# DNVT_box4t.net
KiCad netlist of a schematic drawn in EAGLE
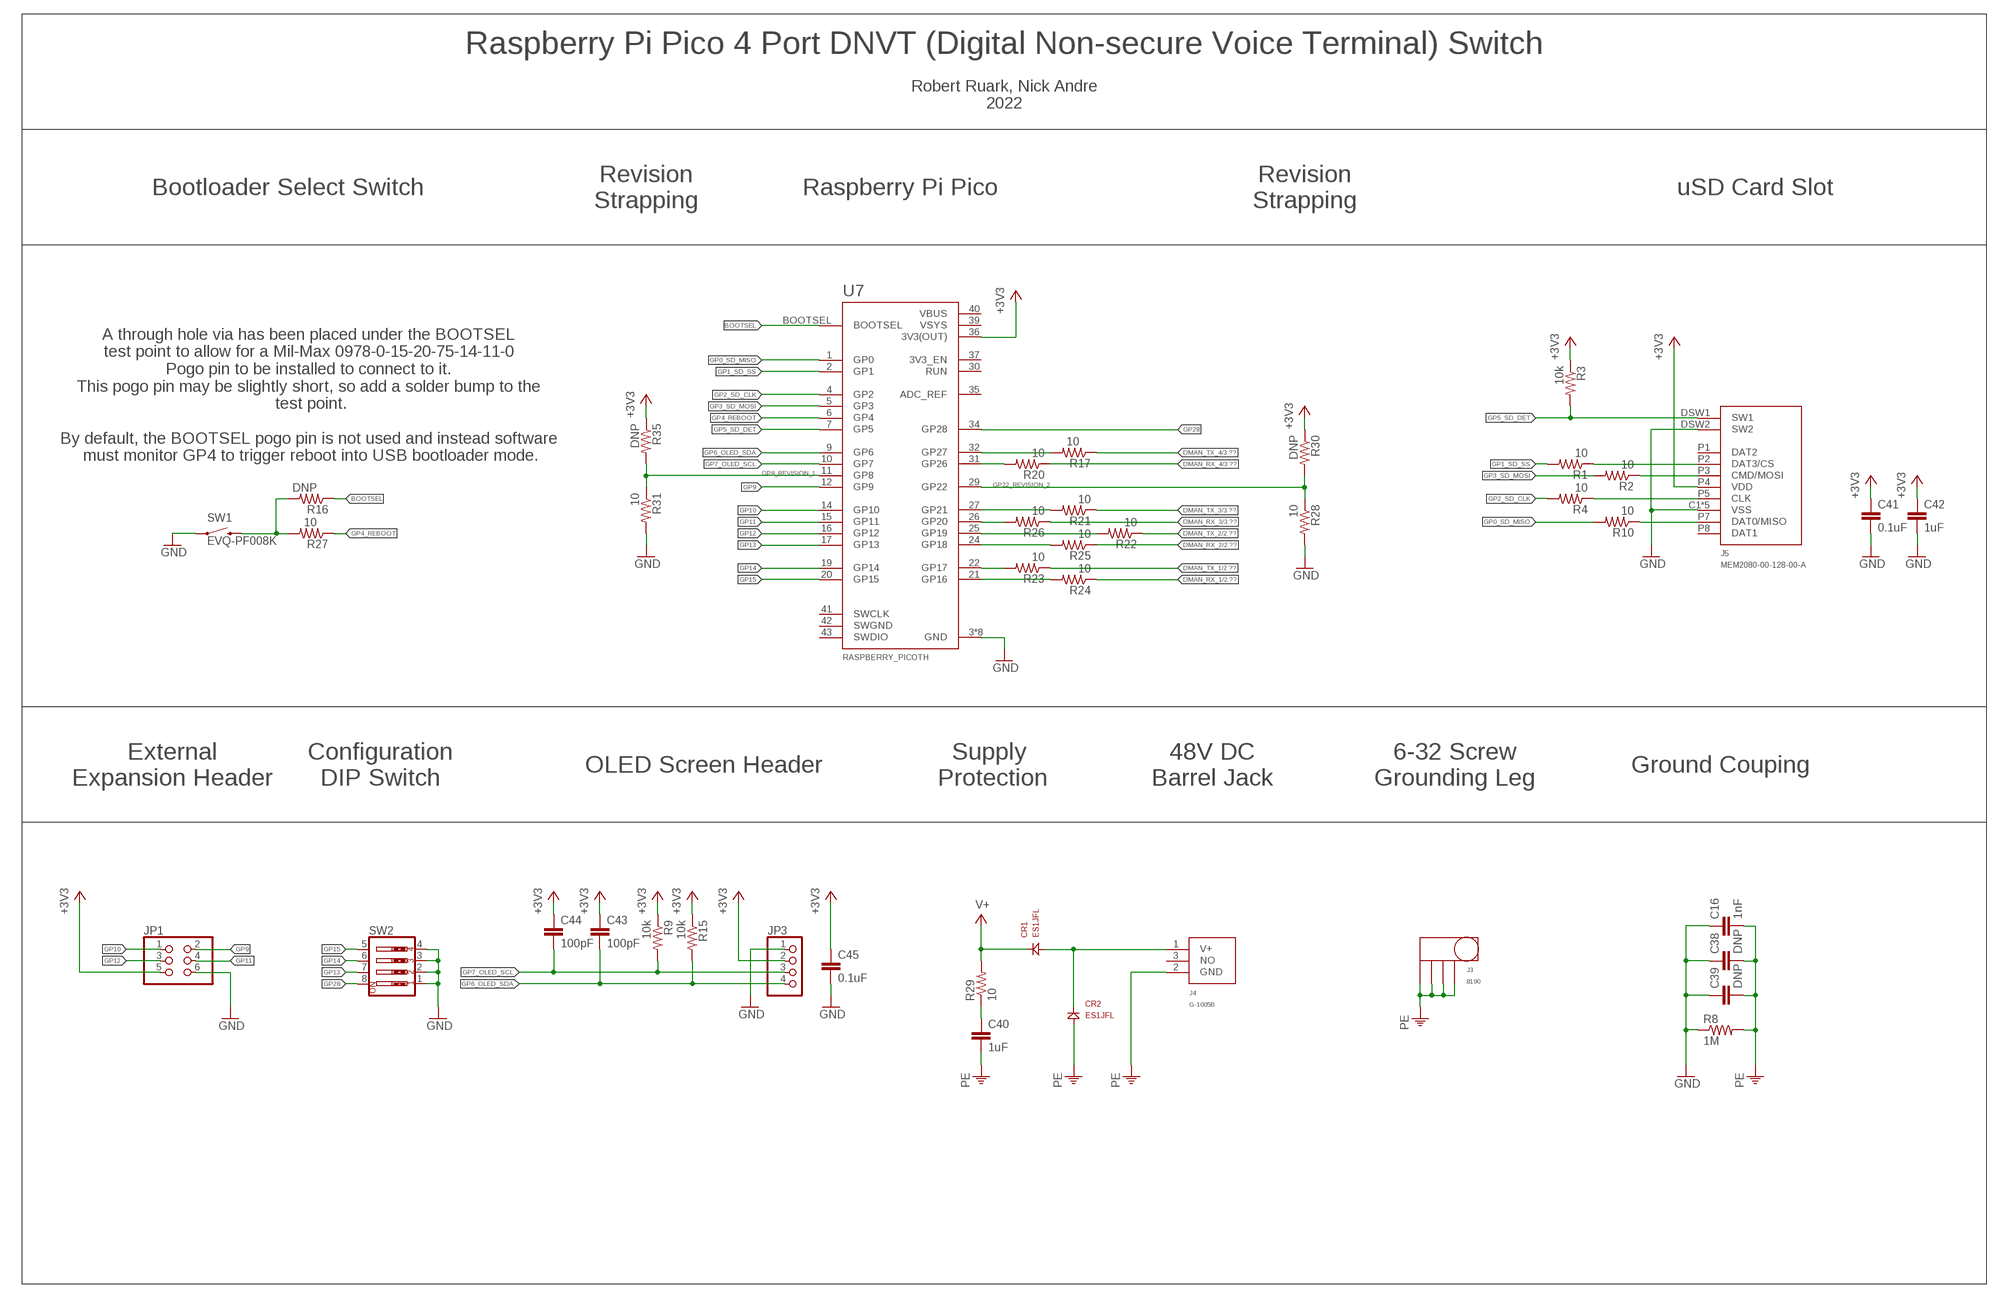
[diagram p0: schematic, sheet 1]
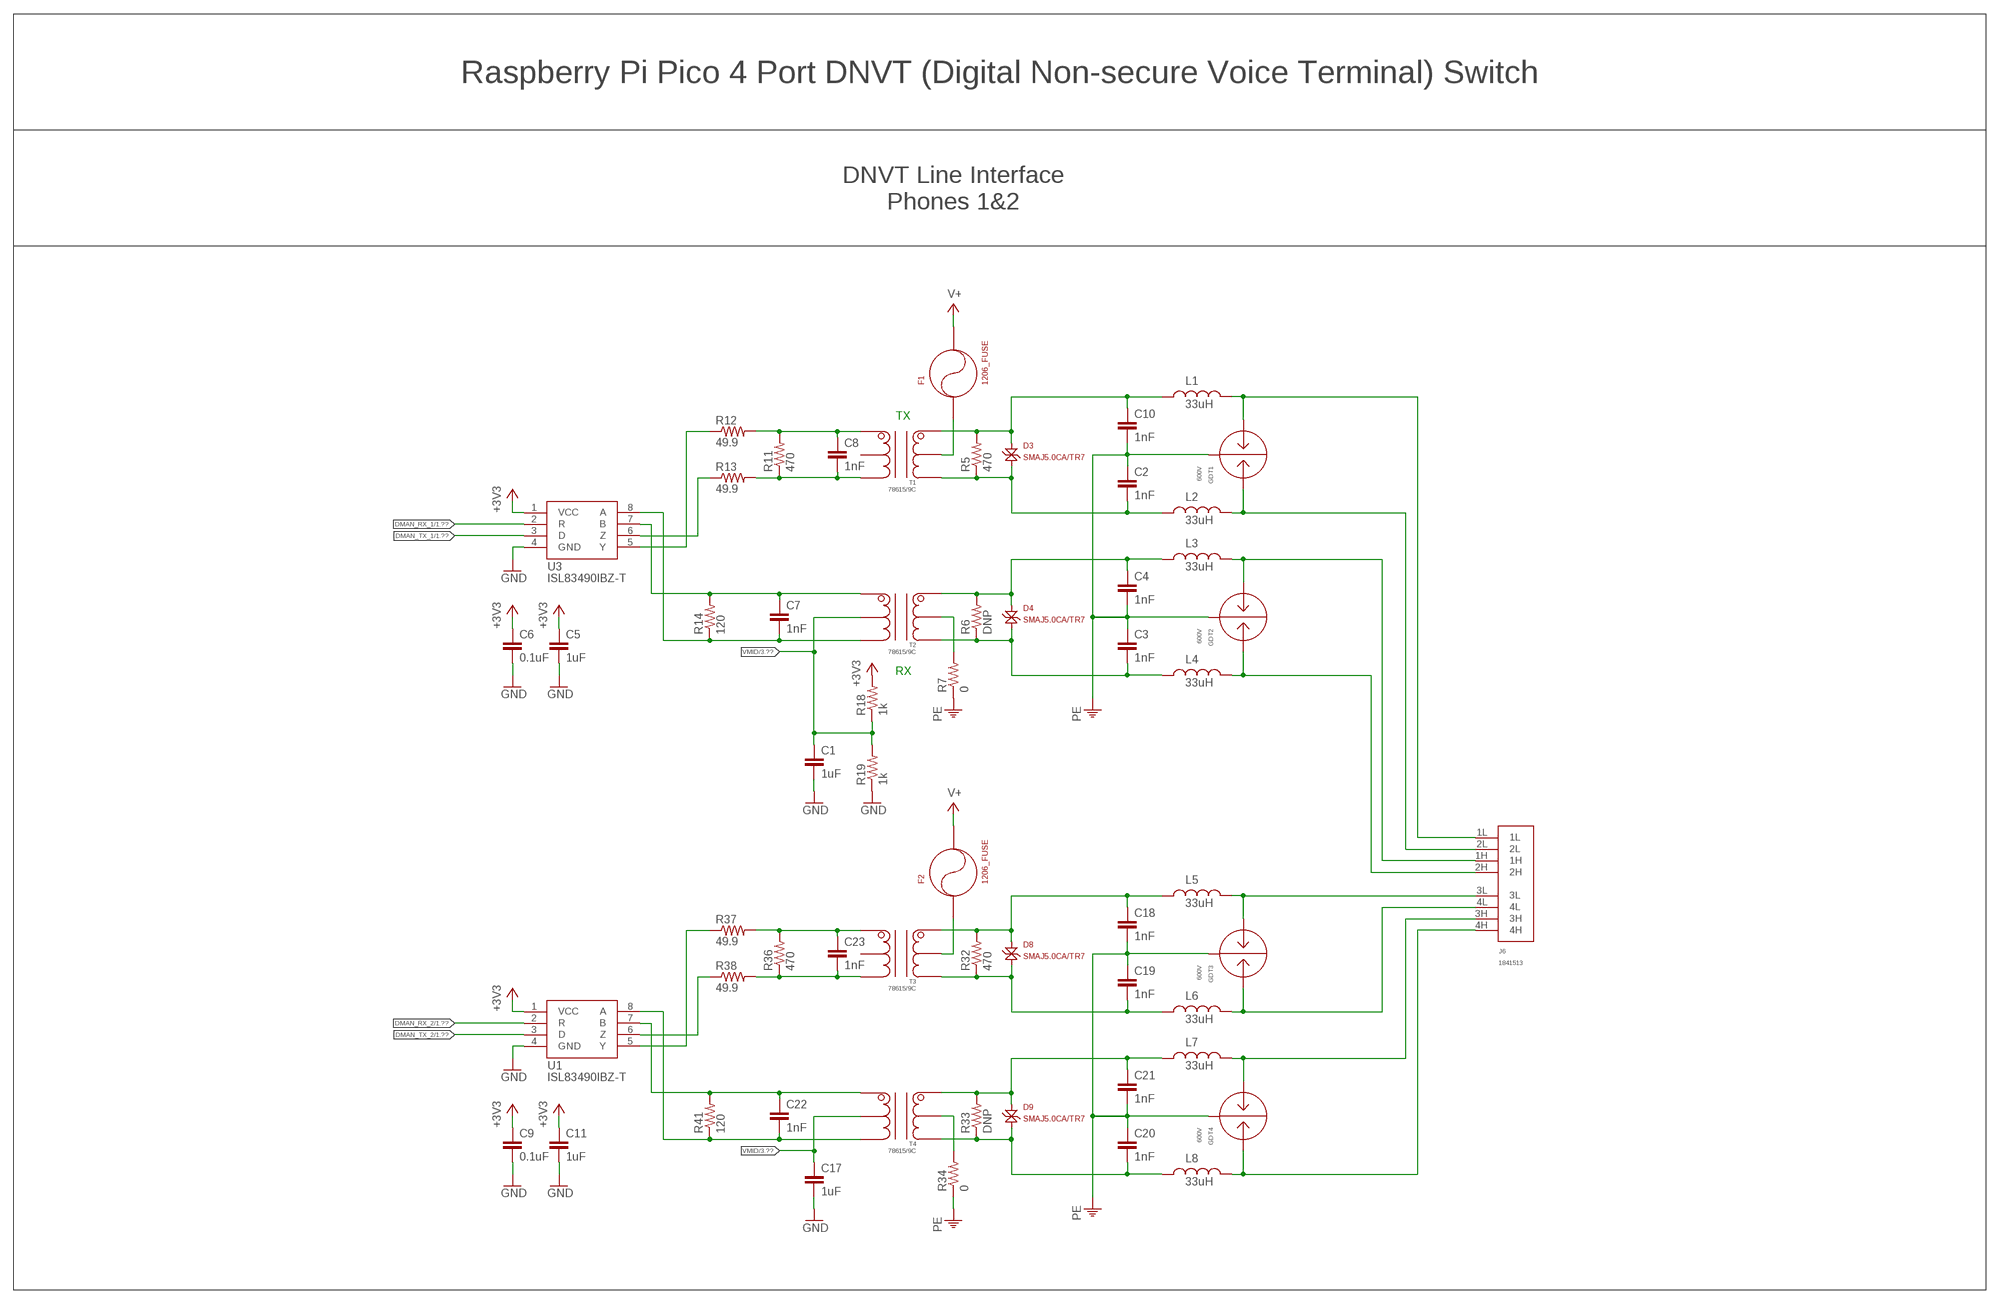
[diagram p1: schematic, sheet 2]
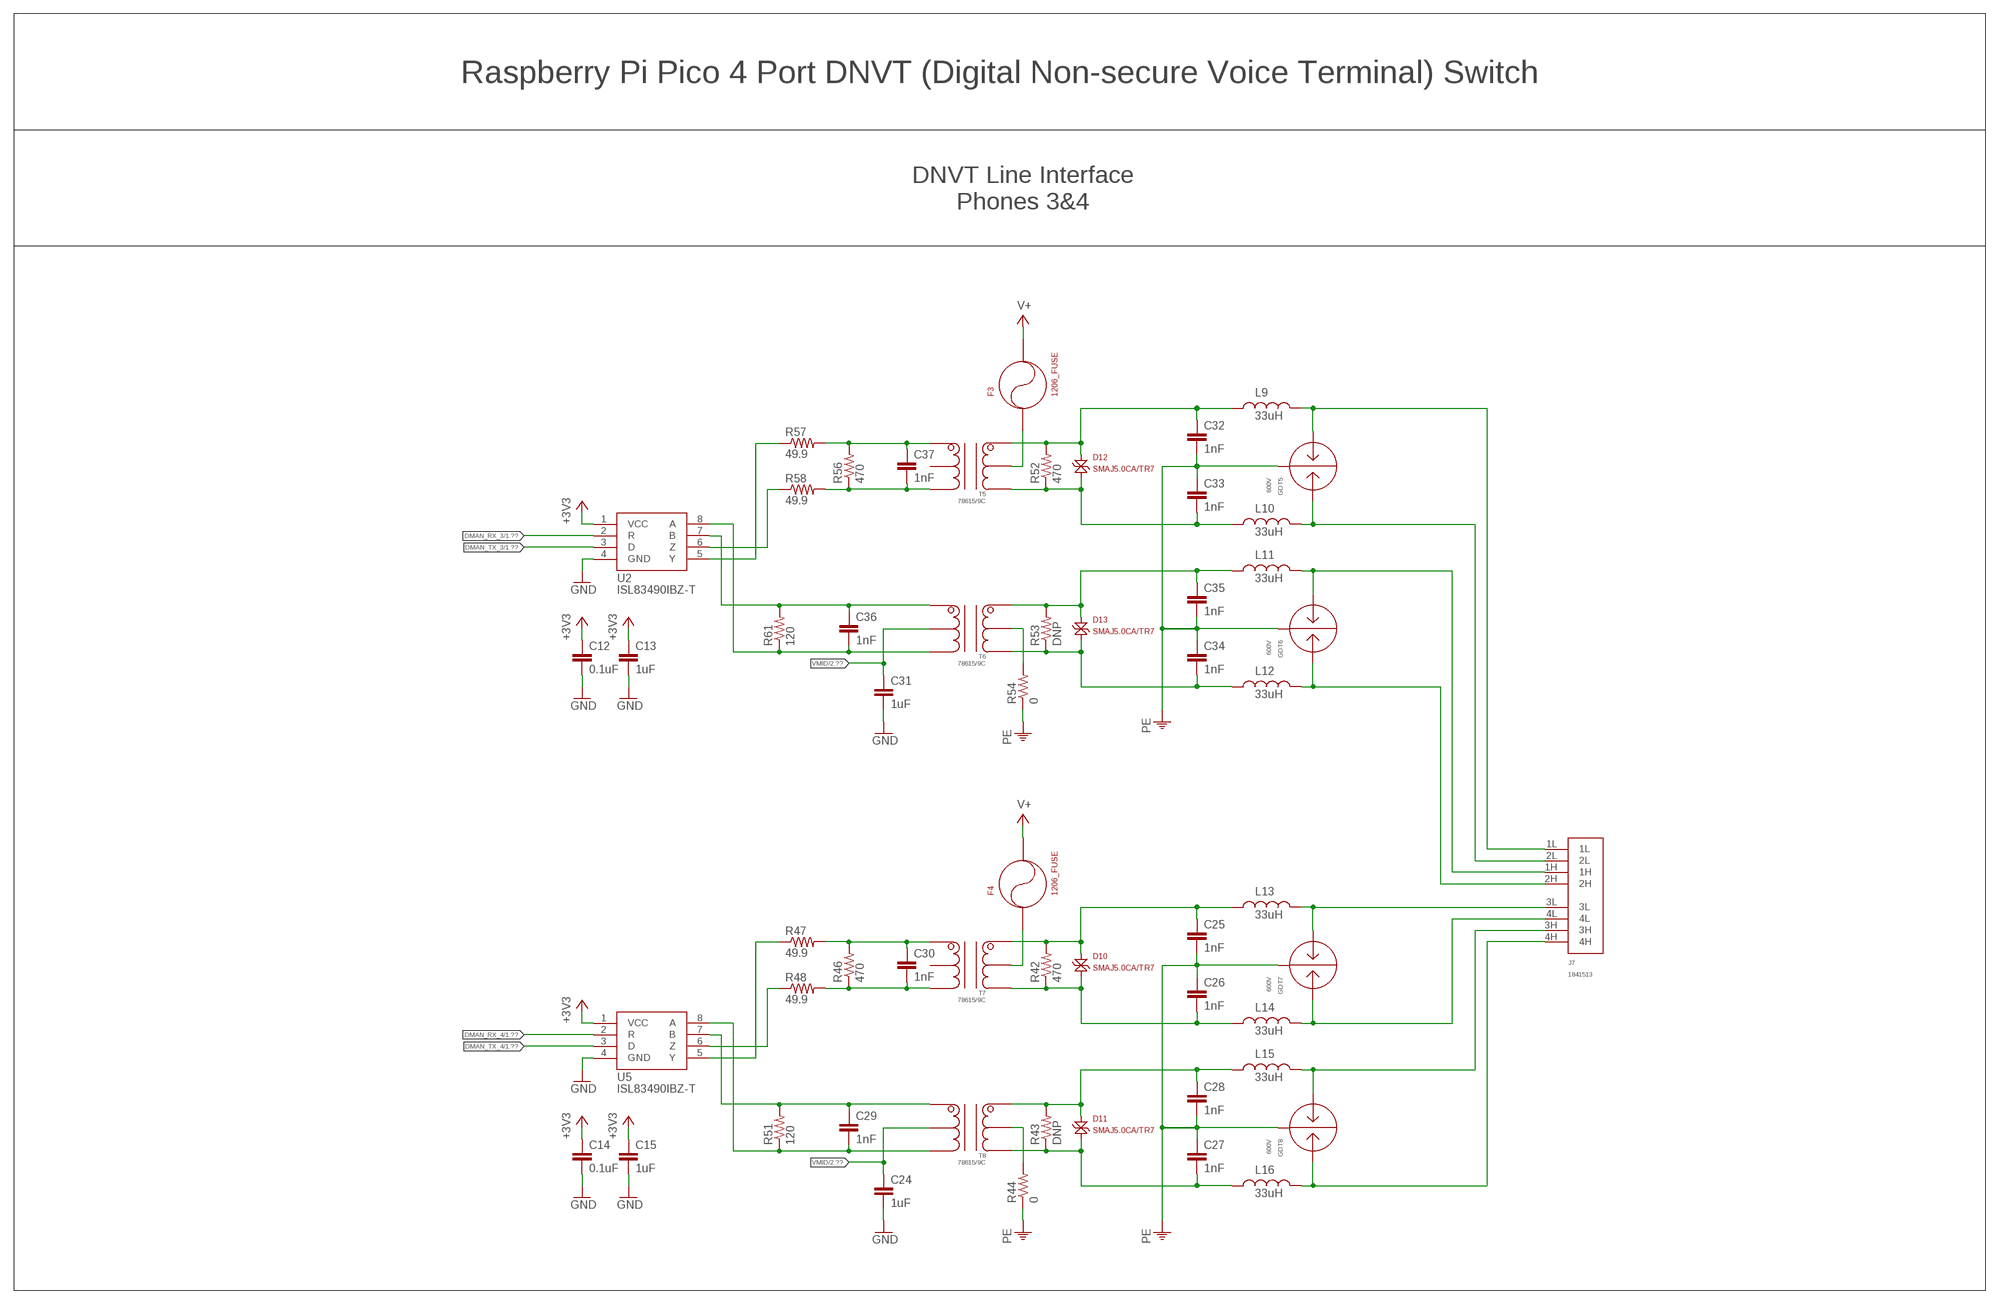
[diagram p2: schematic, sheet 3]

(export (version "E")
  (design (tool "Eeschema 10.0.6"))
  (components
    (comp (ref "C1")
      (value "1uF")
      (footprint "eagle-import:0805")
      (libsource (lib "eagle-import") (part "0805_CAPACITOR"))
    )
    (comp (ref "C2")
      (value "1nF")
      (footprint "eagle-import:0805")
      (libsource (lib "eagle-import") (part "0805_CAPACITOR"))
    )
    (comp (ref "C3")
      (value "1nF")
      (footprint "eagle-import:0805")
      (libsource (lib "eagle-import") (part "0805_CAPACITOR"))
    )
    (comp (ref "C4")
      (value "1nF")
      (footprint "eagle-import:0805")
      (libsource (lib "eagle-import") (part "0805_CAPACITOR"))
    )
    (comp (ref "C5")
      (value "1uF")
      (footprint "eagle-import:0805")
      (libsource (lib "eagle-import") (part "0805_CAPACITOR"))
    )
    (comp (ref "C6")
      (value "0.1uF")
      (footprint "eagle-import:0603")
      (libsource (lib "eagle-import") (part "0603_CAPACITOR"))
    )
    (comp (ref "C7")
      (value "1nF")
      (footprint "eagle-import:0805")
      (libsource (lib "eagle-import") (part "0805_CAPACITOR"))
    )
    (comp (ref "C8")
      (value "1nF")
      (footprint "eagle-import:0805")
      (libsource (lib "eagle-import") (part "0805_CAPACITOR"))
    )
    (comp (ref "C9")
      (value "0.1uF")
      (footprint "eagle-import:0603")
      (libsource (lib "eagle-import") (part "0603_CAPACITOR"))
    )
    (comp (ref "C10")
      (value "1nF")
      (footprint "eagle-import:0805")
      (libsource (lib "eagle-import") (part "0805_CAPACITOR"))
    )
    (comp (ref "C11")
      (value "1uF")
      (footprint "eagle-import:0805")
      (libsource (lib "eagle-import") (part "0805_CAPACITOR"))
    )
    (comp (ref "C17")
      (value "1uF")
      (footprint "eagle-import:0805")
      (libsource (lib "eagle-import") (part "0805_CAPACITOR"))
    )
    (comp (ref "C18")
      (value "1nF")
      (footprint "eagle-import:0805")
      (libsource (lib "eagle-import") (part "0805_CAPACITOR"))
    )
    (comp (ref "C19")
      (value "1nF")
      (footprint "eagle-import:0805")
      (libsource (lib "eagle-import") (part "0805_CAPACITOR"))
    )
    (comp (ref "C20")
      (value "1nF")
      (footprint "eagle-import:0805")
      (libsource (lib "eagle-import") (part "0805_CAPACITOR"))
    )
    (comp (ref "C21")
      (value "1nF")
      (footprint "eagle-import:0805")
      (libsource (lib "eagle-import") (part "0805_CAPACITOR"))
    )
    (comp (ref "C22")
      (value "1nF")
      (footprint "eagle-import:0805")
      (libsource (lib "eagle-import") (part "0805_CAPACITOR"))
    )
    (comp (ref "C23")
      (value "1nF")
      (footprint "eagle-import:0805")
      (libsource (lib "eagle-import") (part "0805_CAPACITOR"))
    )
    (comp (ref "D3")
      (value "SMAJ5.0CA/TR7")
      (footprint "eagle-import:DO-214AC_NO_POL")
      (libsource (lib "eagle-import") (part "SMAJ5.0CA/TR7"))
    )
    (comp (ref "D4")
      (value "SMAJ5.0CA/TR7")
      (footprint "eagle-import:DO-214AC_NO_POL")
      (libsource (lib "eagle-import") (part "SMAJ5.0CA/TR7"))
    )
    (comp (ref "D8")
      (value "SMAJ5.0CA/TR7")
      (footprint "eagle-import:DO-214AC_NO_POL")
      (libsource (lib "eagle-import") (part "SMAJ5.0CA/TR7"))
    )
    (comp (ref "D9")
      (value "SMAJ5.0CA/TR7")
      (footprint "eagle-import:DO-214AC_NO_POL")
      (libsource (lib "eagle-import") (part "SMAJ5.0CA/TR7"))
    )
    (comp (ref "F1")
      (value "1206_FUSE")
      (footprint "eagle-import:1206")
      (libsource (lib "eagle-import") (part "1206_FUSE"))
    )
    (comp (ref "F2")
      (value "1206_FUSE")
      (footprint "eagle-import:1206")
      (libsource (lib "eagle-import") (part "1206_FUSE"))
    )
    (comp (ref "GDT1")
      (value "600V")
      (footprint "eagle-import:2036_GDT")
      (fields (field (name "PARTNO") "2036-60-SM-RPLFCT-ND"))
      (libsource (lib "eagle-import") (part "2036-60-SM-RPLF"))
    )
    (comp (ref "GDT2")
      (value "600V")
      (footprint "eagle-import:2036_GDT")
      (fields (field (name "PARTNO") "2036-60-SM-RPLFCT-ND"))
      (libsource (lib "eagle-import") (part "2036-60-SM-RPLF"))
    )
    (comp (ref "GDT3")
      (value "600V")
      (footprint "eagle-import:2036_GDT")
      (fields (field (name "PARTNO") "2036-60-SM-RPLFCT-ND"))
      (libsource (lib "eagle-import") (part "2036-60-SM-RPLF"))
    )
    (comp (ref "GDT4")
      (value "600V")
      (footprint "eagle-import:2036_GDT")
      (fields (field (name "PARTNO") "2036-60-SM-RPLFCT-ND"))
      (libsource (lib "eagle-import") (part "2036-60-SM-RPLF"))
    )
    (comp (ref "J6")
      (value "1841513")
      (footprint "eagle-import:1841513")
      (fields (field (name "PARTNO") "277-10317-ND"))
      (libsource (lib "eagle-import") (part "1841513"))
    )
    (comp (ref "L1")
      (value "33uH")
      (footprint "eagle-import:SDR0403")
      (fields (field (name "PARTNO") "SDR0403-330KLCT-ND"))
      (libsource (lib "eagle-import") (part "SDR0403-330KL"))
    )
    (comp (ref "L2")
      (value "33uH")
      (footprint "eagle-import:SDR0403")
      (fields (field (name "PARTNO") "SDR0403-330KLCT-ND"))
      (libsource (lib "eagle-import") (part "SDR0403-330KL"))
    )
    (comp (ref "L3")
      (value "33uH")
      (footprint "eagle-import:SDR0403")
      (fields (field (name "PARTNO") "SDR0403-330KLCT-ND"))
      (libsource (lib "eagle-import") (part "SDR0403-330KL"))
    )
    (comp (ref "L4")
      (value "33uH")
      (footprint "eagle-import:SDR0403")
      (fields (field (name "PARTNO") "SDR0403-330KLCT-ND"))
      (libsource (lib "eagle-import") (part "SDR0403-330KL"))
    )
    (comp (ref "L5")
      (value "33uH")
      (footprint "eagle-import:SDR0403")
      (fields (field (name "PARTNO") "SDR0403-330KLCT-ND"))
      (libsource (lib "eagle-import") (part "SDR0403-330KL"))
    )
    (comp (ref "L6")
      (value "33uH")
      (footprint "eagle-import:SDR0403")
      (fields (field (name "PARTNO") "SDR0403-330KLCT-ND"))
      (libsource (lib "eagle-import") (part "SDR0403-330KL"))
    )
    (comp (ref "L7")
      (value "33uH")
      (footprint "eagle-import:SDR0403")
      (fields (field (name "PARTNO") "SDR0403-330KLCT-ND"))
      (libsource (lib "eagle-import") (part "SDR0403-330KL"))
    )
    (comp (ref "L8")
      (value "33uH")
      (footprint "eagle-import:SDR0403")
      (fields (field (name "PARTNO") "SDR0403-330KLCT-ND"))
      (libsource (lib "eagle-import") (part "SDR0403-330KL"))
    )
    (comp (ref "R5")
      (value "470")
      (footprint "eagle-import:R0805")
      (libsource (lib "eagle-import") (part "R-US_R0805"))
    )
    (comp (ref "R6")
      (value "DNP")
      (footprint "eagle-import:R0805")
      (libsource (lib "eagle-import") (part "R-US_R0805"))
    )
    (comp (ref "R7")
      (value "0")
      (footprint "eagle-import:R0805")
      (libsource (lib "eagle-import") (part "R-US_R0805"))
    )
    (comp (ref "R11")
      (value "470")
      (footprint "eagle-import:R0805")
      (libsource (lib "eagle-import") (part "R-US_R0805"))
    )
    (comp (ref "R12")
      (value "49.9")
      (footprint "eagle-import:R0805")
      (libsource (lib "eagle-import") (part "R-US_R0805"))
    )
    (comp (ref "R13")
      (value "49.9")
      (footprint "eagle-import:R0805")
      (libsource (lib "eagle-import") (part "R-US_R0805"))
    )
    (comp (ref "R14")
      (value "120")
      (footprint "eagle-import:1206")
      (libsource (lib "eagle-import") (part "1206_RESISTOR"))
    )
    (comp (ref "R18")
      (value "1k")
      (footprint "eagle-import:0603")
      (libsource (lib "eagle-import") (part "0603_RESISTOR"))
    )
    (comp (ref "R19")
      (value "1k")
      (footprint "eagle-import:0603")
      (libsource (lib "eagle-import") (part "0603_RESISTOR"))
    )
    (comp (ref "R32")
      (value "470")
      (footprint "eagle-import:R0805")
      (libsource (lib "eagle-import") (part "R-US_R0805"))
    )
    (comp (ref "R33")
      (value "DNP")
      (footprint "eagle-import:R0805")
      (libsource (lib "eagle-import") (part "R-US_R0805"))
    )
    (comp (ref "R34")
      (value "0")
      (footprint "eagle-import:R0805")
      (libsource (lib "eagle-import") (part "R-US_R0805"))
    )
    (comp (ref "R36")
      (value "470")
      (footprint "eagle-import:R0805")
      (libsource (lib "eagle-import") (part "R-US_R0805"))
    )
    (comp (ref "R37")
      (value "49.9")
      (footprint "eagle-import:R0805")
      (libsource (lib "eagle-import") (part "R-US_R0805"))
    )
    (comp (ref "R38")
      (value "49.9")
      (footprint "eagle-import:R0805")
      (libsource (lib "eagle-import") (part "R-US_R0805"))
    )
    (comp (ref "R41")
      (value "120")
      (footprint "eagle-import:1206")
      (libsource (lib "eagle-import") (part "1206_RESISTOR"))
    )
    (comp (ref "T1")
      (value "78615/9C")
      (footprint "eagle-import:786T")
      (libsource (lib "eagle-import") (part "78615/9C"))
    )
    (comp (ref "T2")
      (value "78615/9C")
      (footprint "eagle-import:786T")
      (libsource (lib "eagle-import") (part "78615/9C"))
    )
    (comp (ref "T3")
      (value "78615/9C")
      (footprint "eagle-import:786T")
      (libsource (lib "eagle-import") (part "78615/9C"))
    )
    (comp (ref "T4")
      (value "78615/9C")
      (footprint "eagle-import:786T")
      (libsource (lib "eagle-import") (part "78615/9C"))
    )
    (comp (ref "U1")
      (value "ISL83490IBZ-T")
      (footprint "eagle-import:SOIC8")
      (fields (field (name "PARTNO") "ISL83490IBZ-TCT-ND"))
      (libsource (lib "eagle-import") (part "ISL83490IBZ-T"))
    )
    (comp (ref "U3")
      (value "ISL83490IBZ-T")
      (footprint "eagle-import:SOIC8")
      (fields (field (name "PARTNO") "ISL83490IBZ-TCT-ND"))
      (libsource (lib "eagle-import") (part "ISL83490IBZ-T"))
    )
    (comp (ref "C12")
      (value "0.1uF")
      (footprint "eagle-import:0603")
      (libsource (lib "eagle-import") (part "0603_CAPACITOR"))
    )
    (comp (ref "C13")
      (value "1uF")
      (footprint "eagle-import:0805")
      (libsource (lib "eagle-import") (part "0805_CAPACITOR"))
    )
    (comp (ref "C14")
      (value "0.1uF")
      (footprint "eagle-import:0603")
      (libsource (lib "eagle-import") (part "0603_CAPACITOR"))
    )
    (comp (ref "C15")
      (value "1uF")
      (footprint "eagle-import:0805")
      (libsource (lib "eagle-import") (part "0805_CAPACITOR"))
    )
    (comp (ref "C24")
      (value "1uF")
      (footprint "eagle-import:0805")
      (libsource (lib "eagle-import") (part "0805_CAPACITOR"))
    )
    (comp (ref "C25")
      (value "1nF")
      (footprint "eagle-import:0805")
      (libsource (lib "eagle-import") (part "0805_CAPACITOR"))
    )
    (comp (ref "C26")
      (value "1nF")
      (footprint "eagle-import:0805")
      (libsource (lib "eagle-import") (part "0805_CAPACITOR"))
    )
    (comp (ref "C27")
      (value "1nF")
      (footprint "eagle-import:0805")
      (libsource (lib "eagle-import") (part "0805_CAPACITOR"))
    )
    (comp (ref "C28")
      (value "1nF")
      (footprint "eagle-import:0805")
      (libsource (lib "eagle-import") (part "0805_CAPACITOR"))
    )
    (comp (ref "C29")
      (value "1nF")
      (footprint "eagle-import:0805")
      (libsource (lib "eagle-import") (part "0805_CAPACITOR"))
    )
    (comp (ref "C30")
      (value "1nF")
      (footprint "eagle-import:0805")
      (libsource (lib "eagle-import") (part "0805_CAPACITOR"))
    )
    (comp (ref "C31")
      (value "1uF")
      (footprint "eagle-import:0805")
      (libsource (lib "eagle-import") (part "0805_CAPACITOR"))
    )
    (comp (ref "C32")
      (value "1nF")
      (footprint "eagle-import:0805")
      (libsource (lib "eagle-import") (part "0805_CAPACITOR"))
    )
    (comp (ref "C33")
      (value "1nF")
      (footprint "eagle-import:0805")
      (libsource (lib "eagle-import") (part "0805_CAPACITOR"))
    )
    (comp (ref "C34")
      (value "1nF")
      (footprint "eagle-import:0805")
      (libsource (lib "eagle-import") (part "0805_CAPACITOR"))
    )
    (comp (ref "C35")
      (value "1nF")
      (footprint "eagle-import:0805")
      (libsource (lib "eagle-import") (part "0805_CAPACITOR"))
    )
    (comp (ref "C36")
      (value "1nF")
      (footprint "eagle-import:0805")
      (libsource (lib "eagle-import") (part "0805_CAPACITOR"))
    )
    (comp (ref "C37")
      (value "1nF")
      (footprint "eagle-import:0805")
      (libsource (lib "eagle-import") (part "0805_CAPACITOR"))
    )
    (comp (ref "D10")
      (value "SMAJ5.0CA/TR7")
      (footprint "eagle-import:DO-214AC_NO_POL")
      (libsource (lib "eagle-import") (part "SMAJ5.0CA/TR7"))
    )
    (comp (ref "D11")
      (value "SMAJ5.0CA/TR7")
      (footprint "eagle-import:DO-214AC_NO_POL")
      (libsource (lib "eagle-import") (part "SMAJ5.0CA/TR7"))
    )
    (comp (ref "D12")
      (value "SMAJ5.0CA/TR7")
      (footprint "eagle-import:DO-214AC_NO_POL")
      (libsource (lib "eagle-import") (part "SMAJ5.0CA/TR7"))
    )
    (comp (ref "D13")
      (value "SMAJ5.0CA/TR7")
      (footprint "eagle-import:DO-214AC_NO_POL")
      (libsource (lib "eagle-import") (part "SMAJ5.0CA/TR7"))
    )
    (comp (ref "F3")
      (value "1206_FUSE")
      (footprint "eagle-import:1206")
      (libsource (lib "eagle-import") (part "1206_FUSE"))
    )
    (comp (ref "F4")
      (value "1206_FUSE")
      (footprint "eagle-import:1206")
      (libsource (lib "eagle-import") (part "1206_FUSE"))
    )
    (comp (ref "GDT5")
      (value "600V")
      (footprint "eagle-import:2036_GDT")
      (fields (field (name "PARTNO") "2036-60-SM-RPLFCT-ND"))
      (libsource (lib "eagle-import") (part "2036-60-SM-RPLF"))
    )
    (comp (ref "GDT6")
      (value "600V")
      (footprint "eagle-import:2036_GDT")
      (fields (field (name "PARTNO") "2036-60-SM-RPLFCT-ND"))
      (libsource (lib "eagle-import") (part "2036-60-SM-RPLF"))
    )
    (comp (ref "GDT7")
      (value "600V")
      (footprint "eagle-import:2036_GDT")
      (fields (field (name "PARTNO") "2036-60-SM-RPLFCT-ND"))
      (libsource (lib "eagle-import") (part "2036-60-SM-RPLF"))
    )
    (comp (ref "GDT8")
      (value "600V")
      (footprint "eagle-import:2036_GDT")
      (fields (field (name "PARTNO") "2036-60-SM-RPLFCT-ND"))
      (libsource (lib "eagle-import") (part "2036-60-SM-RPLF"))
    )
    (comp (ref "J7")
      (value "1841513")
      (footprint "eagle-import:1841513")
      (fields (field (name "PARTNO") "277-10317-ND"))
      (libsource (lib "eagle-import") (part "1841513"))
    )
    (comp (ref "L9")
      (value "33uH")
      (footprint "eagle-import:SDR0403")
      (fields (field (name "PARTNO") "SDR0403-330KLCT-ND"))
      (libsource (lib "eagle-import") (part "SDR0403-330KL"))
    )
    (comp (ref "L10")
      (value "33uH")
      (footprint "eagle-import:SDR0403")
      (fields (field (name "PARTNO") "SDR0403-330KLCT-ND"))
      (libsource (lib "eagle-import") (part "SDR0403-330KL"))
    )
    (comp (ref "L11")
      (value "33uH")
      (footprint "eagle-import:SDR0403")
      (fields (field (name "PARTNO") "SDR0403-330KLCT-ND"))
      (libsource (lib "eagle-import") (part "SDR0403-330KL"))
    )
    (comp (ref "L12")
      (value "33uH")
      (footprint "eagle-import:SDR0403")
      (fields (field (name "PARTNO") "SDR0403-330KLCT-ND"))
      (libsource (lib "eagle-import") (part "SDR0403-330KL"))
    )
    (comp (ref "L13")
      (value "33uH")
      (footprint "eagle-import:SDR0403")
      (fields (field (name "PARTNO") "SDR0403-330KLCT-ND"))
      (libsource (lib "eagle-import") (part "SDR0403-330KL"))
    )
    (comp (ref "L14")
      (value "33uH")
      (footprint "eagle-import:SDR0403")
      (fields (field (name "PARTNO") "SDR0403-330KLCT-ND"))
      (libsource (lib "eagle-import") (part "SDR0403-330KL"))
    )
    (comp (ref "L15")
      (value "33uH")
      (footprint "eagle-import:SDR0403")
      (fields (field (name "PARTNO") "SDR0403-330KLCT-ND"))
      (libsource (lib "eagle-import") (part "SDR0403-330KL"))
    )
    (comp (ref "L16")
      (value "33uH")
      (footprint "eagle-import:SDR0403")
      (fields (field (name "PARTNO") "SDR0403-330KLCT-ND"))
      (libsource (lib "eagle-import") (part "SDR0403-330KL"))
    )
    (comp (ref "R42")
      (value "470")
      (footprint "eagle-import:R0805")
      (libsource (lib "eagle-import") (part "R-US_R0805"))
    )
    (comp (ref "R43")
      (value "DNP")
      (footprint "eagle-import:R0805")
      (libsource (lib "eagle-import") (part "R-US_R0805"))
    )
    (comp (ref "R44")
      (value "0")
      (footprint "eagle-import:R0805")
      (libsource (lib "eagle-import") (part "R-US_R0805"))
    )
    (comp (ref "R46")
      (value "470")
      (footprint "eagle-import:R0805")
      (libsource (lib "eagle-import") (part "R-US_R0805"))
    )
    (comp (ref "R47")
      (value "49.9")
      (footprint "eagle-import:R0805")
      (libsource (lib "eagle-import") (part "R-US_R0805"))
    )
    (comp (ref "R48")
      (value "49.9")
      (footprint "eagle-import:R0805")
      (libsource (lib "eagle-import") (part "R-US_R0805"))
    )
    (comp (ref "R51")
      (value "120")
      (footprint "eagle-import:1206")
      (libsource (lib "eagle-import") (part "1206_RESISTOR"))
    )
    (comp (ref "R52")
      (value "470")
      (footprint "eagle-import:R0805")
      (libsource (lib "eagle-import") (part "R-US_R0805"))
    )
    (comp (ref "R53")
      (value "DNP")
      (footprint "eagle-import:R0805")
      (libsource (lib "eagle-import") (part "R-US_R0805"))
    )
    (comp (ref "R54")
      (value "0")
      (footprint "eagle-import:R0805")
      (libsource (lib "eagle-import") (part "R-US_R0805"))
    )
    (comp (ref "R56")
      (value "470")
      (footprint "eagle-import:R0805")
      (libsource (lib "eagle-import") (part "R-US_R0805"))
    )
    (comp (ref "R57")
      (value "49.9")
      (footprint "eagle-import:R0805")
      (libsource (lib "eagle-import") (part "R-US_R0805"))
    )
    (comp (ref "R58")
      (value "49.9")
      (footprint "eagle-import:R0805")
      (libsource (lib "eagle-import") (part "R-US_R0805"))
    )
    (comp (ref "R61")
      (value "120")
      (footprint "eagle-import:1206")
      (libsource (lib "eagle-import") (part "1206_RESISTOR"))
    )
    (comp (ref "T5")
      (value "78615/9C")
      (footprint "eagle-import:786T")
      (libsource (lib "eagle-import") (part "78615/9C"))
    )
    (comp (ref "T6")
      (value "78615/9C")
      (footprint "eagle-import:786T")
      (libsource (lib "eagle-import") (part "78615/9C"))
    )
    (comp (ref "T7")
      (value "78615/9C")
      (footprint "eagle-import:786T")
      (libsource (lib "eagle-import") (part "78615/9C"))
    )
    (comp (ref "T8")
      (value "78615/9C")
      (footprint "eagle-import:786T")
      (libsource (lib "eagle-import") (part "78615/9C"))
    )
    (comp (ref "U2")
      (value "ISL83490IBZ-T")
      (footprint "eagle-import:SOIC8")
      (fields (field (name "PARTNO") "ISL83490IBZ-TCT-ND"))
      (libsource (lib "eagle-import") (part "ISL83490IBZ-T"))
    )
    (comp (ref "U5")
      (value "ISL83490IBZ-T")
      (footprint "eagle-import:SOIC8")
      (fields (field (name "PARTNO") "ISL83490IBZ-TCT-ND"))
      (libsource (lib "eagle-import") (part "ISL83490IBZ-T"))
    )
    (comp (ref "C16")
      (value "1nF")
      (footprint "eagle-import:1206")
      (libsource (lib "eagle-import") (part "1206_CAPACITOR"))
    )
    (comp (ref "C38")
      (value "DNP")
      (footprint "eagle-import:1206")
      (libsource (lib "eagle-import") (part "1206_CAPACITOR"))
    )
    (comp (ref "C39")
      (value "DNP")
      (footprint "eagle-import:1206")
      (libsource (lib "eagle-import") (part "1206_CAPACITOR"))
    )
    (comp (ref "C40")
      (value "1uF")
      (footprint "eagle-import:1206")
      (libsource (lib "eagle-import") (part "1206_CAPACITOR"))
    )
    (comp (ref "C41")
      (value "0.1uF")
      (footprint "eagle-import:0603")
      (libsource (lib "eagle-import") (part "0603_CAPACITOR"))
    )
    (comp (ref "C42")
      (value "1uF")
      (footprint "eagle-import:0805")
      (libsource (lib "eagle-import") (part "0805_CAPACITOR"))
    )
    (comp (ref "C43")
      (value "100pF")
      (footprint "eagle-import:0603")
      (libsource (lib "eagle-import") (part "0603_CAPACITOR"))
    )
    (comp (ref "C44")
      (value "100pF")
      (footprint "eagle-import:0603")
      (libsource (lib "eagle-import") (part "0603_CAPACITOR"))
    )
    (comp (ref "C45")
      (value "0.1uF")
      (footprint "eagle-import:0603")
      (libsource (lib "eagle-import") (part "0603_CAPACITOR"))
    )
    (comp (ref "CR1")
      (value "ES1JFL")
      (footprint "eagle-import:SOD123(AK)")
      (fields (field (name "PARTNO") "ES1JFLCT-ND"))
      (libsource (lib "eagle-import") (part "ES1JFL"))
    )
    (comp (ref "CR2")
      (value "ES1JFL")
      (footprint "eagle-import:SOD123(AK)")
      (fields (field (name "PARTNO") "ES1JFLCT-ND"))
      (libsource (lib "eagle-import") (part "ES1JFL"))
    )
    (comp (ref "J3")
      (value "8190")
      (footprint "eagle-import:7781")
      (fields (field (name "PARTNO") "36-8190-ND"))
      (libsource (lib "eagle-import") (part "8190"))
    )
    (comp (ref "J4")
      (value "G-1005B")
      (footprint "eagle-import:G-1005B")
      (fields (field (name "PARTNO") "1939-G-1005B-ND"))
      (libsource (lib "eagle-import") (part "G-1005B"))
    )
    (comp (ref "J5")
      (value "MEM2080-00-128-00-A")
      (footprint "eagle-import:MEM2080")
      (fields (field (name "PARTNO") "2073-MEM2080-00-128-00-ACT-ND"))
      (libsource (lib "eagle-import") (part "MEM2080-00-128-00-A"))
    )
    (comp (ref "JP1")
      (value "PINHD-2X3/90")
      (footprint "eagle-import:2X03_90")
      (libsource (lib "eagle-import") (part "PINHD-2X3/90"))
    )
    (comp (ref "JP3")
      (value "PINHD-1X4")
      (footprint "eagle-import:1X04")
      (libsource (lib "eagle-import") (part "PINHD-1X4"))
    )
    (comp (ref "R1")
      (value "10")
      (footprint "eagle-import:0603")
      (libsource (lib "eagle-import") (part "0603_RESISTOR"))
    )
    (comp (ref "R2")
      (value "10")
      (footprint "eagle-import:0603")
      (libsource (lib "eagle-import") (part "0603_RESISTOR"))
    )
    (comp (ref "R3")
      (value "10k")
      (footprint "eagle-import:0603")
      (libsource (lib "eagle-import") (part "0603_RESISTOR"))
    )
    (comp (ref "R4")
      (value "10")
      (footprint "eagle-import:0603")
      (libsource (lib "eagle-import") (part "0603_RESISTOR"))
    )
    (comp (ref "R8")
      (value "1M")
      (footprint "eagle-import:1206")
      (libsource (lib "eagle-import") (part "1206_RESISTOR"))
    )
    (comp (ref "R9")
      (value "10k")
      (footprint "eagle-import:0603")
      (libsource (lib "eagle-import") (part "0603_RESISTOR"))
    )
    (comp (ref "R10")
      (value "10")
      (footprint "eagle-import:0603")
      (libsource (lib "eagle-import") (part "0603_RESISTOR"))
    )
    (comp (ref "R15")
      (value "10k")
      (footprint "eagle-import:0603")
      (libsource (lib "eagle-import") (part "0603_RESISTOR"))
    )
    (comp (ref "R16")
      (value "DNP")
      (footprint "eagle-import:0603")
      (libsource (lib "eagle-import") (part "0603_RESISTOR"))
    )
    (comp (ref "R17")
      (value "10")
      (footprint "eagle-import:0603")
      (libsource (lib "eagle-import") (part "0603_RESISTOR"))
    )
    (comp (ref "R20")
      (value "10")
      (footprint "eagle-import:0603")
      (libsource (lib "eagle-import") (part "0603_RESISTOR"))
    )
    (comp (ref "R21")
      (value "10")
      (footprint "eagle-import:0603")
      (libsource (lib "eagle-import") (part "0603_RESISTOR"))
    )
    (comp (ref "R22")
      (value "10")
      (footprint "eagle-import:0603")
      (libsource (lib "eagle-import") (part "0603_RESISTOR"))
    )
    (comp (ref "R23")
      (value "10")
      (footprint "eagle-import:0603")
      (libsource (lib "eagle-import") (part "0603_RESISTOR"))
    )
    (comp (ref "R24")
      (value "10")
      (footprint "eagle-import:0603")
      (libsource (lib "eagle-import") (part "0603_RESISTOR"))
    )
    (comp (ref "R25")
      (value "10")
      (footprint "eagle-import:0603")
      (libsource (lib "eagle-import") (part "0603_RESISTOR"))
    )
    (comp (ref "R26")
      (value "10")
      (footprint "eagle-import:0603")
      (libsource (lib "eagle-import") (part "0603_RESISTOR"))
    )
    (comp (ref "R27")
      (value "10")
      (footprint "eagle-import:0603")
      (libsource (lib "eagle-import") (part "0603_RESISTOR"))
    )
    (comp (ref "R28")
      (value "10")
      (footprint "eagle-import:0603")
      (libsource (lib "eagle-import") (part "0603_RESISTOR"))
    )
    (comp (ref "R29")
      (value "10")
      (footprint "eagle-import:1206")
      (libsource (lib "eagle-import") (part "1206_RESISTOR"))
    )
    (comp (ref "R30")
      (value "DNP")
      (footprint "eagle-import:0603")
      (libsource (lib "eagle-import") (part "0603_RESISTOR"))
    )
    (comp (ref "R31")
      (value "10")
      (footprint "eagle-import:0603")
      (libsource (lib "eagle-import") (part "0603_RESISTOR"))
    )
    (comp (ref "R35")
      (value "DNP")
      (footprint "eagle-import:0603")
      (libsource (lib "eagle-import") (part "0603_RESISTOR"))
    )
    (comp (ref "SW1")
      (value "EVQ-PF008K")
      (footprint "eagle-import:EVQ-PF008K")
      (fields (field (name "PARTNO") "P10880S-ND"))
      (libsource (lib "eagle-import") (part "EVQ-PF008K"))
    )
    (comp (ref "SW2")
      (value "SW_DIP-4")
      (footprint "eagle-import:EDG-04")
      (libsource (lib "eagle-import") (part "SW_DIP-4"))
    )
    (comp (ref "U7")
      (value "RASPBERRY_PICOTH")
      (footprint "eagle-import:PICO-PKG-TH")
      (libsource (lib "eagle-import") (part "RASPBERRY_PICOTH"))
    )
  )
  (nets
    (net (code "1") (name "+3V3") (class "Default")
      (node (ref "C11") (pin "1") (pinfunction "1_1") (pintype "passive"))
      (node (ref "C12") (pin "1") (pinfunction "1_1") (pintype "passive"))
      (node (ref "C13") (pin "1") (pinfunction "1_1") (pintype "passive"))
      (node (ref "C14") (pin "1") (pinfunction "1_1") (pintype "passive"))
      (node (ref "C15") (pin "1") (pinfunction "1_1") (pintype "passive"))
      (node (ref "C41") (pin "1") (pinfunction "1_1") (pintype "passive"))
      (node (ref "C42") (pin "1") (pinfunction "1_1") (pintype "passive"))
      (node (ref "C43") (pin "1") (pinfunction "1_1") (pintype "passive"))
      (node (ref "C44") (pin "1") (pinfunction "1_1") (pintype "passive"))
      (node (ref "C45") (pin "1") (pinfunction "1_1") (pintype "passive"))
      (node (ref "C5") (pin "1") (pinfunction "1_1") (pintype "passive"))
      (node (ref "C6") (pin "1") (pinfunction "1_1") (pintype "passive"))
      (node (ref "C9") (pin "1") (pinfunction "1_1") (pintype "passive"))
      (node (ref "J5") (pin "P4") (pinfunction "VDD_P4") (pintype "bidirectional"))
      (node (ref "JP1") (pin "5") (pinfunction "5_5") (pintype "passive"))
      (node (ref "JP3") (pin "2") (pinfunction "2_2") (pintype "passive"))
      (node (ref "R15") (pin "1") (pinfunction "1_1") (pintype "passive"))
      (node (ref "R18") (pin "2") (pinfunction "2_2") (pintype "passive"))
      (node (ref "R3") (pin "1") (pinfunction "1_1") (pintype "passive"))
      (node (ref "R30") (pin "1") (pinfunction "1_1") (pintype "passive"))
      (node (ref "R35") (pin "1") (pinfunction "1_1") (pintype "passive"))
      (node (ref "R9") (pin "1") (pinfunction "1_1") (pintype "passive"))
      (node (ref "U1") (pin "1") (pinfunction "VCC_1") (pintype "bidirectional"))
      (node (ref "U2") (pin "1") (pinfunction "VCC_1") (pintype "bidirectional"))
      (node (ref "U3") (pin "1") (pinfunction "VCC_1") (pintype "bidirectional"))
      (node (ref "U5") (pin "1") (pinfunction "VCC_1") (pintype "bidirectional"))
      (node (ref "U7") (pin "36") (pinfunction "3V3(OUT)_36") (pintype "power_in"))
    )
    (net (code "2") (name "BOOTSEL") (class "Default")
      (node (ref "R16") (pin "1") (pinfunction "1_1") (pintype "passive"))
      (node (ref "U7") (pin "BOOTSEL") (pinfunction "BOOTSEL_BOOTSEL") (pintype "bidirectional"))
    )
    (net (code "3") (name "DMAN_RX_1") (class "Default")
      (node (ref "R24") (pin "1") (pinfunction "1_1") (pintype "passive"))
      (node (ref "U3") (pin "2") (pinfunction "R_2") (pintype "bidirectional"))
    )
    (net (code "4") (name "DMAN_RX_2") (class "Default")
      (node (ref "R25") (pin "1") (pinfunction "1_1") (pintype "passive"))
      (node (ref "U1") (pin "2") (pinfunction "R_2") (pintype "bidirectional"))
    )
    (net (code "5") (name "DMAN_RX_3") (class "Default")
      (node (ref "R26") (pin "1") (pinfunction "1_1") (pintype "passive"))
      (node (ref "U2") (pin "2") (pinfunction "R_2") (pintype "bidirectional"))
    )
    (net (code "6") (name "DMAN_RX_4") (class "Default")
      (node (ref "R20") (pin "1") (pinfunction "1_1") (pintype "passive"))
      (node (ref "U5") (pin "2") (pinfunction "R_2") (pintype "bidirectional"))
    )
    (net (code "7") (name "DMAN_TX_1") (class "Default")
      (node (ref "R23") (pin "1") (pinfunction "1_1") (pintype "passive"))
      (node (ref "U3") (pin "3") (pinfunction "D_3") (pintype "bidirectional"))
    )
    (net (code "8") (name "DMAN_TX_2") (class "Default")
      (node (ref "R22") (pin "1") (pinfunction "1_1") (pintype "passive"))
      (node (ref "U1") (pin "3") (pinfunction "D_3") (pintype "bidirectional"))
    )
    (net (code "9") (name "DMAN_TX_3") (class "Default")
      (node (ref "R21") (pin "1") (pinfunction "1_1") (pintype "passive"))
      (node (ref "U2") (pin "3") (pinfunction "D_3") (pintype "bidirectional"))
    )
    (net (code "10") (name "DMAN_TX_4") (class "Default")
      (node (ref "R17") (pin "1") (pinfunction "1_1") (pintype "passive"))
      (node (ref "U5") (pin "3") (pinfunction "D_3") (pintype "bidirectional"))
    )
    (net (code "11") (name "GND") (class "Default")
      (node (ref "C1") (pin "2") (pinfunction "2_2") (pintype "passive"))
      (node (ref "C11") (pin "2") (pinfunction "2_2") (pintype "passive"))
      (node (ref "C12") (pin "2") (pinfunction "2_2") (pintype "passive"))
      (node (ref "C13") (pin "2") (pinfunction "2_2") (pintype "passive"))
      (node (ref "C14") (pin "2") (pinfunction "2_2") (pintype "passive"))
      (node (ref "C15") (pin "2") (pinfunction "2_2") (pintype "passive"))
      (node (ref "C16") (pin "1") (pinfunction "1_1") (pintype "passive"))
      (node (ref "C17") (pin "2") (pinfunction "2_2") (pintype "passive"))
      (node (ref "C24") (pin "2") (pinfunction "2_2") (pintype "passive"))
      (node (ref "C31") (pin "2") (pinfunction "2_2") (pintype "passive"))
      (node (ref "C38") (pin "1") (pinfunction "1_1") (pintype "passive"))
      (node (ref "C39") (pin "1") (pinfunction "1_1") (pintype "passive"))
      (node (ref "C41") (pin "2") (pinfunction "2_2") (pintype "passive"))
      (node (ref "C42") (pin "2") (pinfunction "2_2") (pintype "passive"))
      (node (ref "C45") (pin "2") (pinfunction "2_2") (pintype "passive"))
      (node (ref "C5") (pin "2") (pinfunction "2_2") (pintype "passive"))
      (node (ref "C6") (pin "2") (pinfunction "2_2") (pintype "passive"))
      (node (ref "C9") (pin "2") (pinfunction "2_2") (pintype "passive"))
      (node (ref "J5") (pin "C1") (pinfunction "VSS_C1") (pintype "bidirectional"))
      (node (ref "J5") (pin "C2") (pinfunction "VSS_C2") (pintype "bidirectional"))
      (node (ref "J5") (pin "C3") (pinfunction "VSS_C3") (pintype "bidirectional"))
      (node (ref "J5") (pin "C4") (pinfunction "VSS_C4") (pintype "bidirectional"))
      (node (ref "J5") (pin "DSW2") (pinfunction "SW2_DSW2") (pintype "bidirectional"))
      (node (ref "J5") (pin "P6") (pinfunction "VSS_P6") (pintype "bidirectional"))
      (node (ref "JP1") (pin "6") (pinfunction "6_6") (pintype "passive"))
      (node (ref "JP3") (pin "1") (pinfunction "1_1") (pintype "passive"))
      (node (ref "R19") (pin "1") (pinfunction "1_1") (pintype "passive"))
      (node (ref "R28") (pin "2") (pinfunction "2_2") (pintype "passive"))
      (node (ref "R31") (pin "2") (pinfunction "2_2") (pintype "passive"))
      (node (ref "R8") (pin "1") (pinfunction "1_1") (pintype "passive"))
      (node (ref "SW1") (pin "S1") (pinfunction "1_S1") (pintype "passive"))
      (node (ref "SW2") (pin "1") (pinfunction "1_1") (pintype "passive"))
      (node (ref "SW2") (pin "2") (pinfunction "2_2") (pintype "passive"))
      (node (ref "SW2") (pin "3") (pinfunction "3_3") (pintype "passive"))
      (node (ref "SW2") (pin "4") (pinfunction "4_4") (pintype "passive"))
      (node (ref "U1") (pin "4") (pinfunction "GND_4") (pintype "bidirectional"))
      (node (ref "U2") (pin "4") (pinfunction "GND_4") (pintype "bidirectional"))
      (node (ref "U3") (pin "4") (pinfunction "GND_4") (pintype "bidirectional"))
      (node (ref "U5") (pin "4") (pinfunction "GND_4") (pintype "bidirectional"))
      (node (ref "U7") (pin "13") (pinfunction "GND_13") (pintype "power_in"))
      (node (ref "U7") (pin "18") (pinfunction "GND_18") (pintype "power_in"))
      (node (ref "U7") (pin "23") (pinfunction "GND_23") (pintype "power_in"))
      (node (ref "U7") (pin "28") (pinfunction "GND_28") (pintype "power_in"))
      (node (ref "U7") (pin "3") (pinfunction "GND_3") (pintype "power_in"))
      (node (ref "U7") (pin "33") (pinfunction "GND_33") (pintype "power_in"))
      (node (ref "U7") (pin "38") (pinfunction "GND_38") (pintype "power_in"))
      (node (ref "U7") (pin "8") (pinfunction "GND_8") (pintype "power_in"))
    )
    (net (code "12") (name "GP0_SD_MISO") (class "Default")
      (node (ref "R10") (pin "2") (pinfunction "2_2") (pintype "passive"))
      (node (ref "U7") (pin "1") (pinfunction "GP0_1") (pintype "bidirectional"))
    )
    (net (code "13") (name "GP1_SD_SS") (class "Default")
      (node (ref "R1") (pin "2") (pinfunction "2_2") (pintype "passive"))
      (node (ref "U7") (pin "2") (pinfunction "GP1_2") (pintype "bidirectional"))
    )
    (net (code "14") (name "GP2_SD_CLK") (class "Default")
      (node (ref "R4") (pin "2") (pinfunction "2_2") (pintype "passive"))
      (node (ref "U7") (pin "4") (pinfunction "GP2_4") (pintype "bidirectional"))
    )
    (net (code "15") (name "GP3_SD_MOSI") (class "Default")
      (node (ref "R2") (pin "2") (pinfunction "2_2") (pintype "passive"))
      (node (ref "U7") (pin "5") (pinfunction "GP3_5") (pintype "bidirectional"))
    )
    (net (code "16") (name "GP4_REBOOT") (class "Default")
      (node (ref "R27") (pin "1") (pinfunction "1_1") (pintype "passive"))
      (node (ref "U7") (pin "6") (pinfunction "GP4_6") (pintype "bidirectional"))
    )
    (net (code "17") (name "GP5_SD_DET") (class "Default")
      (node (ref "J5") (pin "DSW1") (pinfunction "SW1_DSW1") (pintype "bidirectional"))
      (node (ref "R3") (pin "2") (pinfunction "2_2") (pintype "passive"))
      (node (ref "U7") (pin "7") (pinfunction "GP5_7") (pintype "bidirectional"))
    )
    (net (code "18") (name "GP6_OLED_SDA") (class "Default")
      (node (ref "C43") (pin "2") (pinfunction "2_2") (pintype "passive"))
      (node (ref "JP3") (pin "4") (pinfunction "4_4") (pintype "passive"))
      (node (ref "R15") (pin "2") (pinfunction "2_2") (pintype "passive"))
      (node (ref "U7") (pin "9") (pinfunction "GP6_9") (pintype "bidirectional"))
    )
    (net (code "19") (name "GP7_OLED_SCL") (class "Default")
      (node (ref "C44") (pin "2") (pinfunction "2_2") (pintype "passive"))
      (node (ref "JP3") (pin "3") (pinfunction "3_3") (pintype "passive"))
      (node (ref "R9") (pin "2") (pinfunction "2_2") (pintype "passive"))
      (node (ref "U7") (pin "10") (pinfunction "GP7_10") (pintype "bidirectional"))
    )
    (net (code "20") (name "GP8_REVISION_1") (class "Default")
      (node (ref "R31") (pin "1") (pinfunction "1_1") (pintype "passive"))
      (node (ref "R35") (pin "2") (pinfunction "2_2") (pintype "passive"))
      (node (ref "U7") (pin "11") (pinfunction "GP8_11") (pintype "bidirectional"))
    )
    (net (code "21") (name "GP9") (class "Default")
      (node (ref "JP1") (pin "2") (pinfunction "2_2") (pintype "passive"))
      (node (ref "U7") (pin "12") (pinfunction "GP9_12") (pintype "bidirectional"))
    )
    (net (code "22") (name "GP10") (class "Default")
      (node (ref "JP1") (pin "1") (pinfunction "1_1") (pintype "passive"))
      (node (ref "U7") (pin "14") (pinfunction "GP10_14") (pintype "bidirectional"))
    )
    (net (code "23") (name "GP11") (class "Default")
      (node (ref "JP1") (pin "4") (pinfunction "4_4") (pintype "passive"))
      (node (ref "U7") (pin "15") (pinfunction "GP11_15") (pintype "bidirectional"))
    )
    (net (code "24") (name "GP12") (class "Default")
      (node (ref "JP1") (pin "3") (pinfunction "3_3") (pintype "passive"))
      (node (ref "U7") (pin "16") (pinfunction "GP12_16") (pintype "bidirectional"))
    )
    (net (code "25") (name "GP13") (class "Default")
      (node (ref "SW2") (pin "7") (pinfunction "7_7") (pintype "passive"))
      (node (ref "U7") (pin "17") (pinfunction "GP13_17") (pintype "bidirectional"))
    )
    (net (code "26") (name "GP14") (class "Default")
      (node (ref "SW2") (pin "6") (pinfunction "6_6") (pintype "passive"))
      (node (ref "U7") (pin "19") (pinfunction "GP14_19") (pintype "bidirectional"))
    )
    (net (code "27") (name "GP15") (class "Default")
      (node (ref "SW2") (pin "5") (pinfunction "5_5") (pintype "passive"))
      (node (ref "U7") (pin "20") (pinfunction "GP15_20") (pintype "bidirectional"))
    )
    (net (code "28") (name "GP22_REVISION_2") (class "Default")
      (node (ref "R28") (pin "1") (pinfunction "1_1") (pintype "passive"))
      (node (ref "R30") (pin "2") (pinfunction "2_2") (pintype "passive"))
      (node (ref "U7") (pin "29") (pinfunction "GP22_29") (pintype "bidirectional"))
    )
    (net (code "29") (name "GP28") (class "Default")
      (node (ref "SW2") (pin "8") (pinfunction "8_8") (pintype "passive"))
      (node (ref "U7") (pin "34") (pinfunction "GP28_34") (pintype "bidirectional"))
    )
    (net (code "30") (name "Net-(C8-Pad1)") (class "Default")
      (node (ref "C8") (pin "1") (pinfunction "1_1") (pintype "passive"))
      (node (ref "R11") (pin "2") (pinfunction "2_2") (pintype "passive"))
      (node (ref "R12") (pin "2") (pinfunction "2_2") (pintype "passive"))
      (node (ref "T1") (pin "6") (pinfunction "6_6") (pintype "bidirectional"))
    )
    (net (code "31") (name "Net-(C8-Pad2)") (class "Default")
      (node (ref "C8") (pin "2") (pinfunction "2_2") (pintype "passive"))
      (node (ref "R11") (pin "1") (pinfunction "1_1") (pintype "passive"))
      (node (ref "R13") (pin "2") (pinfunction "2_2") (pintype "passive"))
      (node (ref "T1") (pin "4") (pinfunction "4_4") (pintype "bidirectional"))
    )
    (net (code "32") (name "Net-(C23-Pad1)") (class "Default")
      (node (ref "C23") (pin "1") (pinfunction "1_1") (pintype "passive"))
      (node (ref "R36") (pin "2") (pinfunction "2_2") (pintype "passive"))
      (node (ref "R37") (pin "2") (pinfunction "2_2") (pintype "passive"))
      (node (ref "T3") (pin "6") (pinfunction "6_6") (pintype "bidirectional"))
    )
    (net (code "33") (name "Net-(C23-Pad2)") (class "Default")
      (node (ref "C23") (pin "2") (pinfunction "2_2") (pintype "passive"))
      (node (ref "R36") (pin "1") (pinfunction "1_1") (pintype "passive"))
      (node (ref "R38") (pin "2") (pinfunction "2_2") (pintype "passive"))
      (node (ref "T3") (pin "4") (pinfunction "4_4") (pintype "bidirectional"))
    )
    (net (code "34") (name "Net-(C30-Pad1)") (class "Default")
      (node (ref "C30") (pin "1") (pinfunction "1_1") (pintype "passive"))
      (node (ref "R46") (pin "2") (pinfunction "2_2") (pintype "passive"))
      (node (ref "R47") (pin "2") (pinfunction "2_2") (pintype "passive"))
      (node (ref "T7") (pin "6") (pinfunction "6_6") (pintype "bidirectional"))
    )
    (net (code "35") (name "Net-(C30-Pad2)") (class "Default")
      (node (ref "C30") (pin "2") (pinfunction "2_2") (pintype "passive"))
      (node (ref "R46") (pin "1") (pinfunction "1_1") (pintype "passive"))
      (node (ref "R48") (pin "2") (pinfunction "2_2") (pintype "passive"))
      (node (ref "T7") (pin "4") (pinfunction "4_4") (pintype "bidirectional"))
    )
    (net (code "36") (name "Net-(C37-Pad1)") (class "Default")
      (node (ref "C37") (pin "1") (pinfunction "1_1") (pintype "passive"))
      (node (ref "R56") (pin "2") (pinfunction "2_2") (pintype "passive"))
      (node (ref "R57") (pin "2") (pinfunction "2_2") (pintype "passive"))
      (node (ref "T5") (pin "6") (pinfunction "6_6") (pintype "bidirectional"))
    )
    (net (code "37") (name "Net-(C37-Pad2)") (class "Default")
      (node (ref "C37") (pin "2") (pinfunction "2_2") (pintype "passive"))
      (node (ref "R56") (pin "1") (pinfunction "1_1") (pintype "passive"))
      (node (ref "R58") (pin "2") (pinfunction "2_2") (pintype "passive"))
      (node (ref "T5") (pin "4") (pinfunction "4_4") (pintype "bidirectional"))
    )
    (net (code "38") (name "Net-(C40-Pad1)") (class "Default")
      (node (ref "C40") (pin "1") (pinfunction "1_1") (pintype "passive"))
      (node (ref "R29") (pin "1") (pinfunction "1_1") (pintype "passive"))
    )
    (net (code "39") (name "Net-(D3-K)") (class "Default")
      (node (ref "C10") (pin "1") (pinfunction "1_1") (pintype "passive"))
      (node (ref "D3") (pin "C") (pinfunction "K_C") (pintype "bidirectional"))
      (node (ref "L1") (pin "1") (pinfunction "P$1_1") (pintype "bidirectional"))
      (node (ref "R5") (pin "2") (pinfunction "2_2") (pintype "passive"))
      (node (ref "T1") (pin "1") (pinfunction "1_1") (pintype "bidirectional"))
    )
    (net (code "40") (name "Net-(D4-K)") (class "Default")
      (node (ref "C4") (pin "1") (pinfunction "1_1") (pintype "passive"))
      (node (ref "D4") (pin "C") (pinfunction "K_C") (pintype "bidirectional"))
      (node (ref "L3") (pin "1") (pinfunction "P$1_1") (pintype "bidirectional"))
      (node (ref "R6") (pin "2") (pinfunction "2_2") (pintype "passive"))
      (node (ref "T2") (pin "1") (pinfunction "1_1") (pintype "bidirectional"))
    )
    (net (code "41") (name "Net-(D8-K)") (class "Default")
      (node (ref "C18") (pin "1") (pinfunction "1_1") (pintype "passive"))
      (node (ref "D8") (pin "C") (pinfunction "K_C") (pintype "bidirectional"))
      (node (ref "L5") (pin "1") (pinfunction "P$1_1") (pintype "bidirectional"))
      (node (ref "R32") (pin "2") (pinfunction "2_2") (pintype "passive"))
      (node (ref "T3") (pin "1") (pinfunction "1_1") (pintype "bidirectional"))
    )
    (net (code "42") (name "Net-(D9-K)") (class "Default")
      (node (ref "C21") (pin "1") (pinfunction "1_1") (pintype "passive"))
      (node (ref "D9") (pin "C") (pinfunction "K_C") (pintype "bidirectional"))
      (node (ref "L7") (pin "1") (pinfunction "P$1_1") (pintype "bidirectional"))
      (node (ref "R33") (pin "2") (pinfunction "2_2") (pintype "passive"))
      (node (ref "T4") (pin "1") (pinfunction "1_1") (pintype "bidirectional"))
    )
    (net (code "43") (name "Net-(D10-K)") (class "Default")
      (node (ref "C25") (pin "1") (pinfunction "1_1") (pintype "passive"))
      (node (ref "D10") (pin "C") (pinfunction "K_C") (pintype "bidirectional"))
      (node (ref "L13") (pin "1") (pinfunction "P$1_1") (pintype "bidirectional"))
      (node (ref "R42") (pin "2") (pinfunction "2_2") (pintype "passive"))
      (node (ref "T7") (pin "1") (pinfunction "1_1") (pintype "bidirectional"))
    )
    (net (code "44") (name "Net-(D11-K)") (class "Default")
      (node (ref "C28") (pin "1") (pinfunction "1_1") (pintype "passive"))
      (node (ref "D11") (pin "C") (pinfunction "K_C") (pintype "bidirectional"))
      (node (ref "L15") (pin "1") (pinfunction "P$1_1") (pintype "bidirectional"))
      (node (ref "R43") (pin "2") (pinfunction "2_2") (pintype "passive"))
      (node (ref "T8") (pin "1") (pinfunction "1_1") (pintype "bidirectional"))
    )
    (net (code "45") (name "Net-(D12-K)") (class "Default")
      (node (ref "C32") (pin "1") (pinfunction "1_1") (pintype "passive"))
      (node (ref "D12") (pin "C") (pinfunction "K_C") (pintype "bidirectional"))
      (node (ref "L9") (pin "1") (pinfunction "P$1_1") (pintype "bidirectional"))
      (node (ref "R52") (pin "2") (pinfunction "2_2") (pintype "passive"))
      (node (ref "T5") (pin "1") (pinfunction "1_1") (pintype "bidirectional"))
    )
    (net (code "46") (name "Net-(D13-K)") (class "Default")
      (node (ref "C35") (pin "1") (pinfunction "1_1") (pintype "passive"))
      (node (ref "D13") (pin "C") (pinfunction "K_C") (pintype "bidirectional"))
      (node (ref "L11") (pin "1") (pinfunction "P$1_1") (pintype "bidirectional"))
      (node (ref "R53") (pin "2") (pinfunction "2_2") (pintype "passive"))
      (node (ref "T6") (pin "1") (pinfunction "1_1") (pintype "bidirectional"))
    )
    (net (code "47") (name "Net-(F1-P$1)") (class "Default")
      (node (ref "F1") (pin "1") (pinfunction "P$1_1") (pintype "bidirectional"))
      (node (ref "T1") (pin "2") (pinfunction "2_2") (pintype "bidirectional"))
    )
    (net (code "48") (name "Net-(F2-P$1)") (class "Default")
      (node (ref "F2") (pin "1") (pinfunction "P$1_1") (pintype "bidirectional"))
      (node (ref "T3") (pin "2") (pinfunction "2_2") (pintype "bidirectional"))
    )
    (net (code "49") (name "Net-(F3-P$1)") (class "Default")
      (node (ref "F3") (pin "1") (pinfunction "P$1_1") (pintype "bidirectional"))
      (node (ref "T5") (pin "2") (pinfunction "2_2") (pintype "bidirectional"))
    )
    (net (code "50") (name "Net-(F4-P$1)") (class "Default")
      (node (ref "F4") (pin "1") (pinfunction "P$1_1") (pintype "bidirectional"))
      (node (ref "T7") (pin "2") (pinfunction "2_2") (pintype "bidirectional"))
    )
    (net (code "51") (name "Net-(J4-V+)") (class "Default")
      (node (ref "CR1") (pin "A") (pinfunction "A_A") (pintype "bidirectional"))
      (node (ref "CR2") (pin "K") (pinfunction "K_K") (pintype "bidirectional"))
      (node (ref "J4") (pin "1") (pinfunction "V+_1") (pintype "bidirectional"))
    )
    (net (code "52") (name "Net-(J5-CLK)") (class "Default")
      (node (ref "J5") (pin "P5") (pinfunction "CLK_P5") (pintype "bidirectional"))
      (node (ref "R4") (pin "1") (pinfunction "1_1") (pintype "passive"))
    )
    (net (code "53") (name "Net-(J5-CMD{slash}MOSI)") (class "Default")
      (node (ref "J5") (pin "P3") (pinfunction "CMD/MOSI_P3") (pintype "bidirectional"))
      (node (ref "R2") (pin "1") (pinfunction "1_1") (pintype "passive"))
    )
    (net (code "54") (name "Net-(J5-DAT0{slash}MISO)") (class "Default")
      (node (ref "J5") (pin "P7") (pinfunction "DAT0/MISO_P7") (pintype "bidirectional"))
      (node (ref "R10") (pin "1") (pinfunction "1_1") (pintype "passive"))
    )
    (net (code "55") (name "Net-(J5-DAT3{slash}CS)") (class "Default")
      (node (ref "J5") (pin "P2") (pinfunction "DAT3/CS_P2") (pintype "bidirectional"))
      (node (ref "R1") (pin "1") (pinfunction "1_1") (pintype "passive"))
    )
    (net (code "56") (name "Net-(L1-P$2)") (class "Default")
      (node (ref "GDT1") (pin "L1") (pinfunction "L1_L1") (pintype "bidirectional"))
      (node (ref "J6") (pin "1L") (pinfunction "1L_1L") (pintype "bidirectional"))
      (node (ref "L1") (pin "2") (pinfunction "P$2_2") (pintype "bidirectional"))
    )
    (net (code "57") (name "Net-(L2-P$1)") (class "Default")
      (node (ref "C2") (pin "2") (pinfunction "2_2") (pintype "passive"))
      (node (ref "D3") (pin "A") (pinfunction "A_A") (pintype "bidirectional"))
      (node (ref "L2") (pin "1") (pinfunction "P$1_1") (pintype "bidirectional"))
      (node (ref "R5") (pin "1") (pinfunction "1_1") (pintype "passive"))
      (node (ref "T1") (pin "3") (pinfunction "3_3") (pintype "bidirectional"))
    )
    (net (code "58") (name "Net-(L2-P$2)") (class "Default")
      (node (ref "GDT1") (pin "L2") (pinfunction "L2_L2") (pintype "bidirectional"))
      (node (ref "J6") (pin "2L") (pinfunction "2L_2L") (pintype "bidirectional"))
      (node (ref "L2") (pin "2") (pinfunction "P$2_2") (pintype "bidirectional"))
    )
    (net (code "59") (name "Net-(L3-P$2)") (class "Default")
      (node (ref "GDT2") (pin "L1") (pinfunction "L1_L1") (pintype "bidirectional"))
      (node (ref "J6") (pin "1H") (pinfunction "1H_1H") (pintype "bidirectional"))
      (node (ref "L3") (pin "2") (pinfunction "P$2_2") (pintype "bidirectional"))
    )
    (net (code "60") (name "Net-(L4-P$1)") (class "Default")
      (node (ref "C3") (pin "2") (pinfunction "2_2") (pintype "passive"))
      (node (ref "D4") (pin "A") (pinfunction "A_A") (pintype "bidirectional"))
      (node (ref "L4") (pin "1") (pinfunction "P$1_1") (pintype "bidirectional"))
      (node (ref "R6") (pin "1") (pinfunction "1_1") (pintype "passive"))
      (node (ref "T2") (pin "3") (pinfunction "3_3") (pintype "bidirectional"))
    )
    (net (code "61") (name "Net-(L4-P$2)") (class "Default")
      (node (ref "GDT2") (pin "L2") (pinfunction "L2_L2") (pintype "bidirectional"))
      (node (ref "J6") (pin "2H") (pinfunction "2H_2H") (pintype "bidirectional"))
      (node (ref "L4") (pin "2") (pinfunction "P$2_2") (pintype "bidirectional"))
    )
    (net (code "62") (name "Net-(L5-P$2)") (class "Default")
      (node (ref "GDT3") (pin "L1") (pinfunction "L1_L1") (pintype "bidirectional"))
      (node (ref "J6") (pin "3L") (pinfunction "3L_3L") (pintype "bidirectional"))
      (node (ref "L5") (pin "2") (pinfunction "P$2_2") (pintype "bidirectional"))
    )
    (net (code "63") (name "Net-(L6-P$1)") (class "Default")
      (node (ref "C19") (pin "2") (pinfunction "2_2") (pintype "passive"))
      (node (ref "D8") (pin "A") (pinfunction "A_A") (pintype "bidirectional"))
      (node (ref "L6") (pin "1") (pinfunction "P$1_1") (pintype "bidirectional"))
      (node (ref "R32") (pin "1") (pinfunction "1_1") (pintype "passive"))
      (node (ref "T3") (pin "3") (pinfunction "3_3") (pintype "bidirectional"))
    )
    (net (code "64") (name "Net-(L6-P$2)") (class "Default")
      (node (ref "GDT3") (pin "L2") (pinfunction "L2_L2") (pintype "bidirectional"))
      (node (ref "J6") (pin "4L") (pinfunction "4L_4L") (pintype "bidirectional"))
      (node (ref "L6") (pin "2") (pinfunction "P$2_2") (pintype "bidirectional"))
    )
    (net (code "65") (name "Net-(L7-P$2)") (class "Default")
      (node (ref "GDT4") (pin "L1") (pinfunction "L1_L1") (pintype "bidirectional"))
      (node (ref "J6") (pin "3H") (pinfunction "3H_3H") (pintype "bidirectional"))
      (node (ref "L7") (pin "2") (pinfunction "P$2_2") (pintype "bidirectional"))
    )
    (net (code "66") (name "Net-(L8-P$1)") (class "Default")
      (node (ref "C20") (pin "2") (pinfunction "2_2") (pintype "passive"))
      (node (ref "D9") (pin "A") (pinfunction "A_A") (pintype "bidirectional"))
      (node (ref "L8") (pin "1") (pinfunction "P$1_1") (pintype "bidirectional"))
      (node (ref "R33") (pin "1") (pinfunction "1_1") (pintype "passive"))
      (node (ref "T4") (pin "3") (pinfunction "3_3") (pintype "bidirectional"))
    )
    (net (code "67") (name "Net-(L8-P$2)") (class "Default")
      (node (ref "GDT4") (pin "L2") (pinfunction "L2_L2") (pintype "bidirectional"))
      (node (ref "J6") (pin "4H") (pinfunction "4H_4H") (pintype "bidirectional"))
      (node (ref "L8") (pin "2") (pinfunction "P$2_2") (pintype "bidirectional"))
    )
    (net (code "68") (name "Net-(L9-P$2)") (class "Default")
      (node (ref "GDT5") (pin "L1") (pinfunction "L1_L1") (pintype "bidirectional"))
      (node (ref "J7") (pin "1L") (pinfunction "1L_1L") (pintype "bidirectional"))
      (node (ref "L9") (pin "2") (pinfunction "P$2_2") (pintype "bidirectional"))
    )
    (net (code "69") (name "Net-(L10-P$1)") (class "Default")
      (node (ref "C33") (pin "2") (pinfunction "2_2") (pintype "passive"))
      (node (ref "D12") (pin "A") (pinfunction "A_A") (pintype "bidirectional"))
      (node (ref "L10") (pin "1") (pinfunction "P$1_1") (pintype "bidirectional"))
      (node (ref "R52") (pin "1") (pinfunction "1_1") (pintype "passive"))
      (node (ref "T5") (pin "3") (pinfunction "3_3") (pintype "bidirectional"))
    )
    (net (code "70") (name "Net-(L10-P$2)") (class "Default")
      (node (ref "GDT5") (pin "L2") (pinfunction "L2_L2") (pintype "bidirectional"))
      (node (ref "J7") (pin "2L") (pinfunction "2L_2L") (pintype "bidirectional"))
      (node (ref "L10") (pin "2") (pinfunction "P$2_2") (pintype "bidirectional"))
    )
    (net (code "71") (name "Net-(L11-P$2)") (class "Default")
      (node (ref "GDT6") (pin "L1") (pinfunction "L1_L1") (pintype "bidirectional"))
      (node (ref "J7") (pin "1H") (pinfunction "1H_1H") (pintype "bidirectional"))
      (node (ref "L11") (pin "2") (pinfunction "P$2_2") (pintype "bidirectional"))
    )
    (net (code "72") (name "Net-(L12-P$1)") (class "Default")
      (node (ref "C34") (pin "2") (pinfunction "2_2") (pintype "passive"))
      (node (ref "D13") (pin "A") (pinfunction "A_A") (pintype "bidirectional"))
      (node (ref "L12") (pin "1") (pinfunction "P$1_1") (pintype "bidirectional"))
      (node (ref "R53") (pin "1") (pinfunction "1_1") (pintype "passive"))
      (node (ref "T6") (pin "3") (pinfunction "3_3") (pintype "bidirectional"))
    )
    (net (code "73") (name "Net-(L12-P$2)") (class "Default")
      (node (ref "GDT6") (pin "L2") (pinfunction "L2_L2") (pintype "bidirectional"))
      (node (ref "J7") (pin "2H") (pinfunction "2H_2H") (pintype "bidirectional"))
      (node (ref "L12") (pin "2") (pinfunction "P$2_2") (pintype "bidirectional"))
    )
    (net (code "74") (name "Net-(L13-P$2)") (class "Default")
      (node (ref "GDT7") (pin "L1") (pinfunction "L1_L1") (pintype "bidirectional"))
      (node (ref "J7") (pin "3L") (pinfunction "3L_3L") (pintype "bidirectional"))
      (node (ref "L13") (pin "2") (pinfunction "P$2_2") (pintype "bidirectional"))
    )
    (net (code "75") (name "Net-(L14-P$1)") (class "Default")
      (node (ref "C26") (pin "2") (pinfunction "2_2") (pintype "passive"))
      (node (ref "D10") (pin "A") (pinfunction "A_A") (pintype "bidirectional"))
      (node (ref "L14") (pin "1") (pinfunction "P$1_1") (pintype "bidirectional"))
      (node (ref "R42") (pin "1") (pinfunction "1_1") (pintype "passive"))
      (node (ref "T7") (pin "3") (pinfunction "3_3") (pintype "bidirectional"))
    )
    (net (code "76") (name "Net-(L14-P$2)") (class "Default")
      (node (ref "GDT7") (pin "L2") (pinfunction "L2_L2") (pintype "bidirectional"))
      (node (ref "J7") (pin "4L") (pinfunction "4L_4L") (pintype "bidirectional"))
      (node (ref "L14") (pin "2") (pinfunction "P$2_2") (pintype "bidirectional"))
    )
    (net (code "77") (name "Net-(L15-P$2)") (class "Default")
      (node (ref "GDT8") (pin "L1") (pinfunction "L1_L1") (pintype "bidirectional"))
      (node (ref "J7") (pin "3H") (pinfunction "3H_3H") (pintype "bidirectional"))
      (node (ref "L15") (pin "2") (pinfunction "P$2_2") (pintype "bidirectional"))
    )
    (net (code "78") (name "Net-(L16-P$1)") (class "Default")
      (node (ref "C27") (pin "2") (pinfunction "2_2") (pintype "passive"))
      (node (ref "D11") (pin "A") (pinfunction "A_A") (pintype "bidirectional"))
      (node (ref "L16") (pin "1") (pinfunction "P$1_1") (pintype "bidirectional"))
      (node (ref "R43") (pin "1") (pinfunction "1_1") (pintype "passive"))
      (node (ref "T8") (pin "3") (pinfunction "3_3") (pintype "bidirectional"))
    )
    (net (code "79") (name "Net-(L16-P$2)") (class "Default")
      (node (ref "GDT8") (pin "L2") (pinfunction "L2_L2") (pintype "bidirectional"))
      (node (ref "J7") (pin "4H") (pinfunction "4H_4H") (pintype "bidirectional"))
      (node (ref "L16") (pin "2") (pinfunction "P$2_2") (pintype "bidirectional"))
    )
    (net (code "80") (name "Net-(R7-Pad2)") (class "Default")
      (node (ref "R7") (pin "2") (pinfunction "2_2") (pintype "passive"))
      (node (ref "T2") (pin "2") (pinfunction "2_2") (pintype "bidirectional"))
    )
    (net (code "81") (name "Net-(R34-Pad2)") (class "Default")
      (node (ref "R34") (pin "2") (pinfunction "2_2") (pintype "passive"))
      (node (ref "T4") (pin "2") (pinfunction "2_2") (pintype "bidirectional"))
    )
    (net (code "82") (name "Net-(R44-Pad2)") (class "Default")
      (node (ref "R44") (pin "2") (pinfunction "2_2") (pintype "passive"))
      (node (ref "T8") (pin "2") (pinfunction "2_2") (pintype "bidirectional"))
    )
    (net (code "83") (name "Net-(R54-Pad2)") (class "Default")
      (node (ref "R54") (pin "2") (pinfunction "2_2") (pintype "passive"))
      (node (ref "T6") (pin "2") (pinfunction "2_2") (pintype "bidirectional"))
    )
    (net (code "84") (name "Net-(SW1-2)") (class "Default")
      (node (ref "R16") (pin "2") (pinfunction "2_2") (pintype "passive"))
      (node (ref "R27") (pin "2") (pinfunction "2_2") (pintype "passive"))
      (node (ref "SW1") (pin "S2") (pinfunction "2_S2") (pintype "passive"))
    )
    (net (code "85") (name "Net-(U1-A)") (class "Default")
      (node (ref "C22") (pin "2") (pinfunction "2_2") (pintype "passive"))
      (node (ref "R41") (pin "1") (pinfunction "1_1") (pintype "passive"))
      (node (ref "T4") (pin "4") (pinfunction "4_4") (pintype "bidirectional"))
      (node (ref "U1") (pin "8") (pinfunction "A_8") (pintype "bidirectional"))
    )
    (net (code "86") (name "Net-(U1-B)") (class "Default")
      (node (ref "C22") (pin "1") (pinfunction "1_1") (pintype "passive"))
      (node (ref "R41") (pin "2") (pinfunction "2_2") (pintype "passive"))
      (node (ref "T4") (pin "6") (pinfunction "6_6") (pintype "bidirectional"))
      (node (ref "U1") (pin "7") (pinfunction "B_7") (pintype "bidirectional"))
    )
    (net (code "87") (name "Net-(U1-Y)") (class "Default")
      (node (ref "R37") (pin "1") (pinfunction "1_1") (pintype "passive"))
      (node (ref "U1") (pin "5") (pinfunction "Y_5") (pintype "bidirectional"))
    )
    (net (code "88") (name "Net-(U1-Z)") (class "Default")
      (node (ref "R38") (pin "1") (pinfunction "1_1") (pintype "passive"))
      (node (ref "U1") (pin "6") (pinfunction "Z_6") (pintype "bidirectional"))
    )
    (net (code "89") (name "Net-(U2-A)") (class "Default")
      (node (ref "C36") (pin "2") (pinfunction "2_2") (pintype "passive"))
      (node (ref "R61") (pin "1") (pinfunction "1_1") (pintype "passive"))
      (node (ref "T6") (pin "4") (pinfunction "4_4") (pintype "bidirectional"))
      (node (ref "U2") (pin "8") (pinfunction "A_8") (pintype "bidirectional"))
    )
    (net (code "90") (name "Net-(U2-B)") (class "Default")
      (node (ref "C36") (pin "1") (pinfunction "1_1") (pintype "passive"))
      (node (ref "R61") (pin "2") (pinfunction "2_2") (pintype "passive"))
      (node (ref "T6") (pin "6") (pinfunction "6_6") (pintype "bidirectional"))
      (node (ref "U2") (pin "7") (pinfunction "B_7") (pintype "bidirectional"))
    )
    (net (code "91") (name "Net-(U2-Y)") (class "Default")
      (node (ref "R57") (pin "1") (pinfunction "1_1") (pintype "passive"))
      (node (ref "U2") (pin "5") (pinfunction "Y_5") (pintype "bidirectional"))
    )
    (net (code "92") (name "Net-(U2-Z)") (class "Default")
      (node (ref "R58") (pin "1") (pinfunction "1_1") (pintype "passive"))
      (node (ref "U2") (pin "6") (pinfunction "Z_6") (pintype "bidirectional"))
    )
    (net (code "93") (name "Net-(U3-A)") (class "Default")
      (node (ref "C7") (pin "2") (pinfunction "2_2") (pintype "passive"))
      (node (ref "R14") (pin "1") (pinfunction "1_1") (pintype "passive"))
      (node (ref "T2") (pin "4") (pinfunction "4_4") (pintype "bidirectional"))
      (node (ref "U3") (pin "8") (pinfunction "A_8") (pintype "bidirectional"))
    )
    (net (code "94") (name "Net-(U3-B)") (class "Default")
      (node (ref "C7") (pin "1") (pinfunction "1_1") (pintype "passive"))
      (node (ref "R14") (pin "2") (pinfunction "2_2") (pintype "passive"))
      (node (ref "T2") (pin "6") (pinfunction "6_6") (pintype "bidirectional"))
      (node (ref "U3") (pin "7") (pinfunction "B_7") (pintype "bidirectional"))
    )
    (net (code "95") (name "Net-(U3-Y)") (class "Default")
      (node (ref "R12") (pin "1") (pinfunction "1_1") (pintype "passive"))
      (node (ref "U3") (pin "5") (pinfunction "Y_5") (pintype "bidirectional"))
    )
    (net (code "96") (name "Net-(U3-Z)") (class "Default")
      (node (ref "R13") (pin "1") (pinfunction "1_1") (pintype "passive"))
      (node (ref "U3") (pin "6") (pinfunction "Z_6") (pintype "bidirectional"))
    )
    (net (code "97") (name "Net-(U5-A)") (class "Default")
      (node (ref "C29") (pin "2") (pinfunction "2_2") (pintype "passive"))
      (node (ref "R51") (pin "1") (pinfunction "1_1") (pintype "passive"))
      (node (ref "T8") (pin "4") (pinfunction "4_4") (pintype "bidirectional"))
      (node (ref "U5") (pin "8") (pinfunction "A_8") (pintype "bidirectional"))
    )
    (net (code "98") (name "Net-(U5-B)") (class "Default")
      (node (ref "C29") (pin "1") (pinfunction "1_1") (pintype "passive"))
      (node (ref "R51") (pin "2") (pinfunction "2_2") (pintype "passive"))
      (node (ref "T8") (pin "6") (pinfunction "6_6") (pintype "bidirectional"))
      (node (ref "U5") (pin "7") (pinfunction "B_7") (pintype "bidirectional"))
    )
    (net (code "99") (name "Net-(U5-Y)") (class "Default")
      (node (ref "R47") (pin "1") (pinfunction "1_1") (pintype "passive"))
      (node (ref "U5") (pin "5") (pinfunction "Y_5") (pintype "bidirectional"))
    )
    (net (code "100") (name "Net-(U5-Z)") (class "Default")
      (node (ref "R48") (pin "1") (pinfunction "1_1") (pintype "passive"))
      (node (ref "U5") (pin "6") (pinfunction "Z_6") (pintype "bidirectional"))
    )
    (net (code "101") (name "Net-(U7-GP16)") (class "Default")
      (node (ref "R24") (pin "2") (pinfunction "2_2") (pintype "passive"))
      (node (ref "U7") (pin "21") (pinfunction "GP16_21") (pintype "bidirectional"))
    )
    (net (code "102") (name "Net-(U7-GP17)") (class "Default")
      (node (ref "R23") (pin "2") (pinfunction "2_2") (pintype "passive"))
      (node (ref "U7") (pin "22") (pinfunction "GP17_22") (pintype "bidirectional"))
    )
    (net (code "103") (name "Net-(U7-GP18)") (class "Default")
      (node (ref "R25") (pin "2") (pinfunction "2_2") (pintype "passive"))
      (node (ref "U7") (pin "24") (pinfunction "GP18_24") (pintype "bidirectional"))
    )
    (net (code "104") (name "Net-(U7-GP19)") (class "Default")
      (node (ref "R22") (pin "2") (pinfunction "2_2") (pintype "passive"))
      (node (ref "U7") (pin "25") (pinfunction "GP19_25") (pintype "bidirectional"))
    )
    (net (code "105") (name "Net-(U7-GP20)") (class "Default")
      (node (ref "R26") (pin "2") (pinfunction "2_2") (pintype "passive"))
      (node (ref "U7") (pin "26") (pinfunction "GP20_26") (pintype "bidirectional"))
    )
    (net (code "106") (name "Net-(U7-GP21)") (class "Default")
      (node (ref "R21") (pin "2") (pinfunction "2_2") (pintype "passive"))
      (node (ref "U7") (pin "27") (pinfunction "GP21_27") (pintype "bidirectional"))
    )
    (net (code "107") (name "Net-(U7-GP26)") (class "Default")
      (node (ref "R20") (pin "2") (pinfunction "2_2") (pintype "passive"))
      (node (ref "U7") (pin "31") (pinfunction "GP26_31") (pintype "bidirectional"))
    )
    (net (code "108") (name "Net-(U7-GP27)") (class "Default")
      (node (ref "R17") (pin "2") (pinfunction "2_2") (pintype "passive"))
      (node (ref "U7") (pin "32") (pinfunction "GP27_32") (pintype "bidirectional"))
    )
    (net (code "109") (name "PE") (class "Default")
      (node (ref "C10") (pin "2") (pinfunction "2_2") (pintype "passive"))
      (node (ref "C16") (pin "2") (pinfunction "2_2") (pintype "passive"))
      (node (ref "C18") (pin "2") (pinfunction "2_2") (pintype "passive"))
      (node (ref "C19") (pin "1") (pinfunction "1_1") (pintype "passive"))
      (node (ref "C2") (pin "1") (pinfunction "1_1") (pintype "passive"))
      (node (ref "C20") (pin "1") (pinfunction "1_1") (pintype "passive"))
      (node (ref "C21") (pin "2") (pinfunction "2_2") (pintype "passive"))
      (node (ref "C25") (pin "2") (pinfunction "2_2") (pintype "passive"))
      (node (ref "C26") (pin "1") (pinfunction "1_1") (pintype "passive"))
      (node (ref "C27") (pin "1") (pinfunction "1_1") (pintype "passive"))
      (node (ref "C28") (pin "2") (pinfunction "2_2") (pintype "passive"))
      (node (ref "C3") (pin "1") (pinfunction "1_1") (pintype "passive"))
      (node (ref "C32") (pin "2") (pinfunction "2_2") (pintype "passive"))
      (node (ref "C33") (pin "1") (pinfunction "1_1") (pintype "passive"))
      (node (ref "C34") (pin "1") (pinfunction "1_1") (pintype "passive"))
      (node (ref "C35") (pin "2") (pinfunction "2_2") (pintype "passive"))
      (node (ref "C38") (pin "2") (pinfunction "2_2") (pintype "passive"))
      (node (ref "C39") (pin "2") (pinfunction "2_2") (pintype "passive"))
      (node (ref "C4") (pin "2") (pinfunction "2_2") (pintype "passive"))
      (node (ref "C40") (pin "2") (pinfunction "2_2") (pintype "passive"))
      (node (ref "CR2") (pin "A") (pinfunction "A_A") (pintype "bidirectional"))
      (node (ref "GDT1") (pin "C") (pinfunction "C_C") (pintype "bidirectional"))
      (node (ref "GDT2") (pin "C") (pinfunction "C_C") (pintype "bidirectional"))
      (node (ref "GDT3") (pin "C") (pinfunction "C_C") (pintype "bidirectional"))
      (node (ref "GDT4") (pin "C") (pinfunction "C_C") (pintype "bidirectional"))
      (node (ref "GDT5") (pin "C") (pinfunction "C_C") (pintype "bidirectional"))
      (node (ref "GDT6") (pin "C") (pinfunction "C_C") (pintype "bidirectional"))
      (node (ref "GDT7") (pin "C") (pinfunction "C_C") (pintype "bidirectional"))
      (node (ref "GDT8") (pin "C") (pinfunction "C_C") (pintype "bidirectional"))
      (node (ref "J3") (pin "P$1") (pinfunction "P$1_P$1") (pintype "bidirectional"))
      (node (ref "J3") (pin "P$2") (pinfunction "P$2_P$2") (pintype "bidirectional"))
      (node (ref "J3") (pin "P$3") (pinfunction "P$3_P$3") (pintype "bidirectional"))
      (node (ref "J3") (pin "P$4") (pinfunction "P$4_P$4") (pintype "bidirectional"))
      (node (ref "J4") (pin "2") (pinfunction "GND_2") (pintype "bidirectional"))
      (node (ref "R34") (pin "1") (pinfunction "1_1") (pintype "passive"))
      (node (ref "R44") (pin "1") (pinfunction "1_1") (pintype "passive"))
      (node (ref "R54") (pin "1") (pinfunction "1_1") (pintype "passive"))
      (node (ref "R7") (pin "1") (pinfunction "1_1") (pintype "passive"))
      (node (ref "R8") (pin "2") (pinfunction "2_2") (pintype "passive"))
    )
    (net (code "110") (name "SWGND") (class "Default")
      (node (ref "U7") (pin "42") (pinfunction "SWGND_42") (pintype "power_in"))
    )
    (net (code "111") (name "V+") (class "Default")
      (node (ref "CR1") (pin "K") (pinfunction "K_K") (pintype "bidirectional"))
      (node (ref "F1") (pin "2") (pinfunction "P$2_2") (pintype "bidirectional"))
      (node (ref "F2") (pin "2") (pinfunction "P$2_2") (pintype "bidirectional"))
      (node (ref "F3") (pin "2") (pinfunction "P$2_2") (pintype "bidirectional"))
      (node (ref "F4") (pin "2") (pinfunction "P$2_2") (pintype "bidirectional"))
      (node (ref "R29") (pin "2") (pinfunction "2_2") (pintype "passive"))
    )
    (net (code "112") (name "VBUS") (class "Default")
      (node (ref "U7") (pin "40") (pinfunction "VBUS_40") (pintype "power_in"))
    )
    (net (code "113") (name "VMID") (class "Default")
      (node (ref "C1") (pin "1") (pinfunction "1_1") (pintype "passive"))
      (node (ref "C17") (pin "1") (pinfunction "1_1") (pintype "passive"))
      (node (ref "C24") (pin "1") (pinfunction "1_1") (pintype "passive"))
      (node (ref "C31") (pin "1") (pinfunction "1_1") (pintype "passive"))
      (node (ref "R18") (pin "1") (pinfunction "1_1") (pintype "passive"))
      (node (ref "R19") (pin "2") (pinfunction "2_2") (pintype "passive"))
      (node (ref "T2") (pin "5") (pinfunction "5_5") (pintype "bidirectional"))
      (node (ref "T4") (pin "5") (pinfunction "5_5") (pintype "bidirectional"))
      (node (ref "T6") (pin "5") (pinfunction "5_5") (pintype "bidirectional"))
      (node (ref "T8") (pin "5") (pinfunction "5_5") (pintype "bidirectional"))
    )
    (net (code "114") (name "VSYS") (class "Default")
      (node (ref "U7") (pin "39") (pinfunction "VSYS_39") (pintype "power_in"))
    )
    (net (code "115") (name "unconnected-(J4-NO-Pad3)") (class "Default")
      (node (ref "J4") (pin "3") (pinfunction "NO_3") (pintype "bidirectional"))
    )
    (net (code "116") (name "unconnected-(J5-DAT1-PadP8)") (class "Default")
      (node (ref "J5") (pin "P8") (pinfunction "DAT1_P8") (pintype "bidirectional"))
    )
    (net (code "117") (name "unconnected-(J5-DAT2-PadP1)") (class "Default")
      (node (ref "J5") (pin "P1") (pinfunction "DAT2_P1") (pintype "bidirectional"))
    )
    (net (code "118") (name "unconnected-(T1-Pad5)") (class "Default")
      (node (ref "T1") (pin "5") (pinfunction "5_5") (pintype "bidirectional"))
    )
    (net (code "119") (name "unconnected-(T3-Pad5)") (class "Default")
      (node (ref "T3") (pin "5") (pinfunction "5_5") (pintype "bidirectional"))
    )
    (net (code "120") (name "unconnected-(T5-Pad5)") (class "Default")
      (node (ref "T5") (pin "5") (pinfunction "5_5") (pintype "bidirectional"))
    )
    (net (code "121") (name "unconnected-(T7-Pad5)") (class "Default")
      (node (ref "T7") (pin "5") (pinfunction "5_5") (pintype "bidirectional"))
    )
    (net (code "122") (name "unconnected-(U7-3V3_EN-Pad37)") (class "Default")
      (node (ref "U7") (pin "37") (pinfunction "3V3_EN_37") (pintype "input"))
    )
    (net (code "123") (name "unconnected-(U7-ADC_REF-Pad35)") (class "Default")
      (node (ref "U7") (pin "35") (pinfunction "ADC_REF_35") (pintype "input"))
    )
    (net (code "124") (name "unconnected-(U7-RUN-Pad30)") (class "Default")
      (node (ref "U7") (pin "30") (pinfunction "RUN_30") (pintype "input"))
    )
    (net (code "125") (name "unconnected-(U7-SWCLK-Pad41)") (class "Default")
      (node (ref "U7") (pin "41") (pinfunction "SWCLK_41") (pintype "input"))
    )
    (net (code "126") (name "unconnected-(U7-SWDIO-Pad43)") (class "Default")
      (node (ref "U7") (pin "43") (pinfunction "SWDIO_43") (pintype "bidirectional"))
    )
  )
)
